# MaTouch_ESP32-S3_7_5_Eink_AI_Mic_Array_V.net
KiCad netlist of a schematic drawn in EAGLE
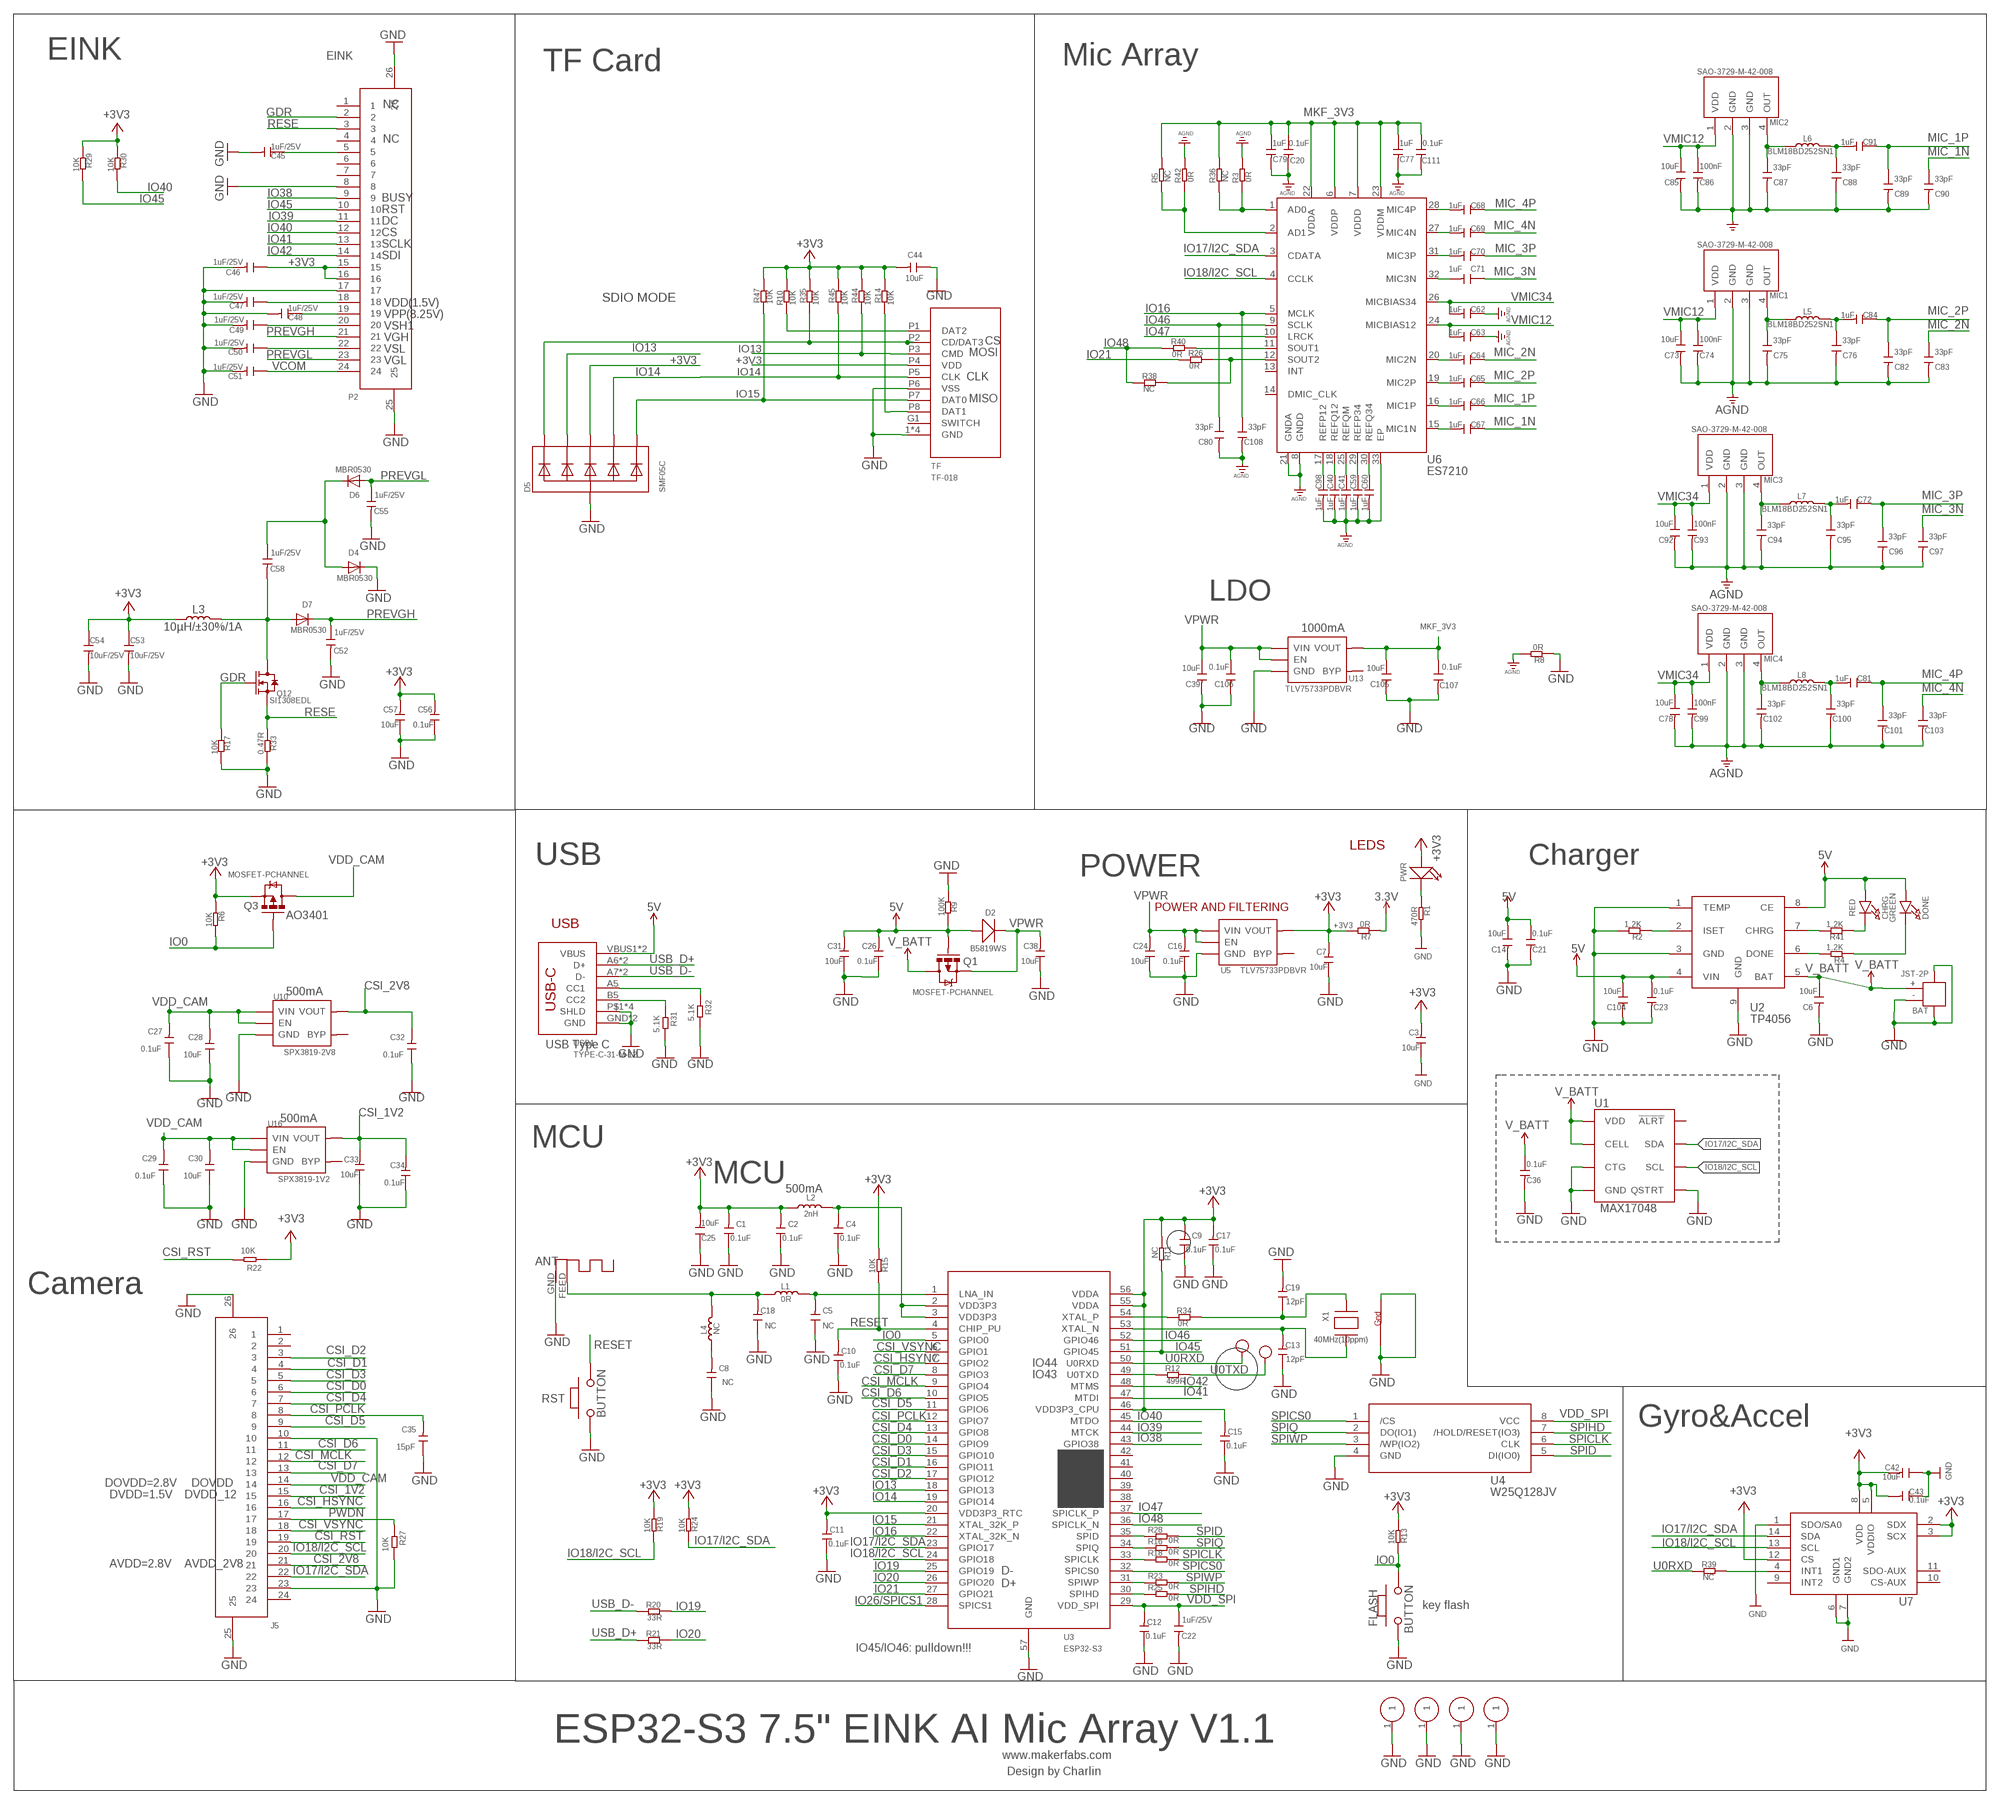
[diagram p0: schematic, sheet 1]

(export (version "E")
  (design (tool "Eeschema 10.0.6"))
  (components
    (comp (ref "ANT1")
      (value "ANTENNA")
      (footprint "eagle-import:RN-ANT")
      (libsource (lib "eagle-import") (part "ANTENNA"))
    )
    (comp (ref "BAT")
      (value "JST-2P")
      (footprint "eagle-import:HW2-SMD-2.0-90D")
      (libsource (lib "eagle-import") (part "JST-2P-SMD'2.0'"))
    )
    (comp (ref "C1")
      (value "0.1uF")
      (footprint "eagle-import:DISCRETE_C0402")
      (libsource (lib "eagle-import") (part "DISCRETE_C-0402"))
    )
    (comp (ref "C2")
      (value "0.1uF")
      (footprint "eagle-import:DISCRETE_C0402")
      (libsource (lib "eagle-import") (part "DISCRETE_C-0402"))
    )
    (comp (ref "C3")
      (value "10uF")
      (footprint "eagle-import:DISCRETE_C0402")
      (libsource (lib "eagle-import") (part "DISCRETE_C-0402"))
    )
    (comp (ref "C4")
      (value "0.1uF")
      (footprint "eagle-import:DISCRETE_C0402")
      (libsource (lib "eagle-import") (part "DISCRETE_C-0402"))
    )
    (comp (ref "C5")
      (value "NC")
      (footprint "eagle-import:DISCRETE_C0402")
      (libsource (lib "eagle-import") (part "DISCRETE_C-0402"))
    )
    (comp (ref "C6")
      (value "10uF")
      (footprint "eagle-import:DISCRETE_C0402")
      (libsource (lib "eagle-import") (part "DISCRETE_C-0402"))
    )
    (comp (ref "C7")
      (value "10uF")
      (footprint "eagle-import:DISCRETE_C0402")
      (libsource (lib "eagle-import") (part "DISCRETE_C-0402"))
    )
    (comp (ref "C8")
      (value "NC")
      (footprint "eagle-import:DISCRETE_C0402")
      (libsource (lib "eagle-import") (part "DISCRETE_C-0402"))
    )
    (comp (ref "C9")
      (value "0.1uF")
      (footprint "eagle-import:DISCRETE_C0402")
      (libsource (lib "eagle-import") (part "DISCRETE_C-0402"))
    )
    (comp (ref "C10")
      (value "0.1uF")
      (footprint "eagle-import:DISCRETE_C0402")
      (libsource (lib "eagle-import") (part "DISCRETE_C-0402"))
    )
    (comp (ref "C11")
      (value "0.1uF")
      (footprint "eagle-import:DISCRETE_C0402")
      (libsource (lib "eagle-import") (part "DISCRETE_C-0402"))
    )
    (comp (ref "C12")
      (value "0.1uF")
      (footprint "eagle-import:DISCRETE_C0402")
      (libsource (lib "eagle-import") (part "DISCRETE_C-0402"))
    )
    (comp (ref "C13")
      (value "12pF")
      (footprint "eagle-import:DISCRETE_C0402")
      (libsource (lib "eagle-import") (part "DISCRETE_C-0402"))
    )
    (comp (ref "C14")
      (value "10uF")
      (footprint "eagle-import:DISCRETE_C0402")
      (libsource (lib "eagle-import") (part "DISCRETE_C-0402"))
    )
    (comp (ref "C15")
      (value "0.1uF")
      (footprint "eagle-import:DISCRETE_C0402")
      (libsource (lib "eagle-import") (part "DISCRETE_C-0402"))
    )
    (comp (ref "C16")
      (value "0.1uF")
      (footprint "eagle-import:DISCRETE_C0402")
      (libsource (lib "eagle-import") (part "DISCRETE_C-0402"))
    )
    (comp (ref "C17")
      (value "0.1uF")
      (footprint "eagle-import:DISCRETE_C0402")
      (libsource (lib "eagle-import") (part "DISCRETE_C-0402"))
    )
    (comp (ref "C18")
      (value "NC")
      (footprint "eagle-import:DISCRETE_C0402")
      (libsource (lib "eagle-import") (part "DISCRETE_C-0402"))
    )
    (comp (ref "C19")
      (value "12pF")
      (footprint "eagle-import:DISCRETE_C0402")
      (libsource (lib "eagle-import") (part "DISCRETE_C-0402"))
    )
    (comp (ref "C20")
      (value "0.1uF")
      (footprint "eagle-import:DISCRETE_C0402")
      (libsource (lib "eagle-import") (part "DISCRETE_C-0402"))
    )
    (comp (ref "C21")
      (value "0.1uF")
      (footprint "eagle-import:DISCRETE_C0402")
      (libsource (lib "eagle-import") (part "DISCRETE_C-0402"))
    )
    (comp (ref "C22")
      (value "1uF/25V")
      (footprint "eagle-import:DISCRETE_C0402")
      (libsource (lib "eagle-import") (part "DISCRETE_C-0402"))
    )
    (comp (ref "C23")
      (value "0.1uF")
      (footprint "eagle-import:DISCRETE_C0402")
      (libsource (lib "eagle-import") (part "DISCRETE_C-0402"))
    )
    (comp (ref "C24")
      (value "10uF")
      (footprint "eagle-import:DISCRETE_C0402")
      (libsource (lib "eagle-import") (part "DISCRETE_C-0402"))
    )
    (comp (ref "C25")
      (value "10uF")
      (footprint "eagle-import:DISCRETE_C0603")
      (libsource (lib "eagle-import") (part "DISCRETE_C-0603"))
    )
    (comp (ref "C26")
      (value "0.1uF")
      (footprint "eagle-import:DISCRETE_C0402")
      (libsource (lib "eagle-import") (part "DISCRETE_C-0402"))
    )
    (comp (ref "C27")
      (value "0.1uF")
      (footprint "eagle-import:DISCRETE_C0402")
      (libsource (lib "eagle-import") (part "DISCRETE_C-0402"))
    )
    (comp (ref "C28")
      (value "10uF")
      (footprint "eagle-import:DISCRETE_C0402")
      (libsource (lib "eagle-import") (part "DISCRETE_C-0402"))
    )
    (comp (ref "C29")
      (value "0.1uF")
      (footprint "eagle-import:DISCRETE_C0402")
      (libsource (lib "eagle-import") (part "DISCRETE_C-0402"))
    )
    (comp (ref "C30")
      (value "10uF")
      (footprint "eagle-import:DISCRETE_C0402")
      (libsource (lib "eagle-import") (part "DISCRETE_C-0402"))
    )
    (comp (ref "C31")
      (value "10uF")
      (footprint "eagle-import:DISCRETE_C0402")
      (libsource (lib "eagle-import") (part "DISCRETE_C-0402"))
    )
    (comp (ref "C32")
      (value "0.1uF")
      (footprint "eagle-import:DISCRETE_C0402")
      (libsource (lib "eagle-import") (part "DISCRETE_C-0402"))
    )
    (comp (ref "C33")
      (value "10uF")
      (footprint "eagle-import:DISCRETE_C0402")
      (libsource (lib "eagle-import") (part "DISCRETE_C-0402"))
    )
    (comp (ref "C34")
      (value "0.1uF")
      (footprint "eagle-import:DISCRETE_C0402")
      (libsource (lib "eagle-import") (part "DISCRETE_C-0402"))
    )
    (comp (ref "C35")
      (value "15pF")
      (footprint "eagle-import:DISCRETE_C0402")
      (libsource (lib "eagle-import") (part "DISCRETE_C-0402"))
    )
    (comp (ref "C36")
      (value "0.1uF")
      (footprint "eagle-import:DISCRETE_C0402")
      (libsource (lib "eagle-import") (part "DISCRETE_C-0402"))
    )
    (comp (ref "C38")
      (value "10uF")
      (footprint "eagle-import:DISCRETE_C0402")
      (libsource (lib "eagle-import") (part "DISCRETE_C-0402"))
    )
    (comp (ref "C39")
      (value "10uF")
      (footprint "eagle-import:DISCRETE_C0402")
      (libsource (lib "eagle-import") (part "DISCRETE_C-0402"))
    )
    (comp (ref "C40")
      (value "1uF")
      (footprint "eagle-import:DISCRETE_C0402")
      (libsource (lib "eagle-import") (part "DISCRETE_C-0402"))
    )
    (comp (ref "C41")
      (value "1uF")
      (footprint "eagle-import:DISCRETE_C0402")
      (libsource (lib "eagle-import") (part "DISCRETE_C-0402"))
    )
    (comp (ref "C42")
      (value "10uF")
      (footprint "eagle-import:DISCRETE_C0402")
      (libsource (lib "eagle-import") (part "DISCRETE_C-0402"))
    )
    (comp (ref "C43")
      (value "0.1uF")
      (footprint "eagle-import:DISCRETE_C0402")
      (libsource (lib "eagle-import") (part "DISCRETE_C-0402"))
    )
    (comp (ref "C44")
      (value "10uF")
      (footprint "eagle-import:DISCRETE_C0402")
      (libsource (lib "eagle-import") (part "DISCRETE_C-0402"))
    )
    (comp (ref "C45")
      (value "1uF/25V")
      (footprint "eagle-import:DISCRETE_C0402")
      (libsource (lib "eagle-import") (part "DISCRETE_C-0402"))
    )
    (comp (ref "C46")
      (value "1uF/25V")
      (footprint "eagle-import:DISCRETE_C0402")
      (libsource (lib "eagle-import") (part "DISCRETE_C-0402"))
    )
    (comp (ref "C47")
      (value "1uF/25V")
      (footprint "eagle-import:DISCRETE_C0402")
      (libsource (lib "eagle-import") (part "DISCRETE_C-0402"))
    )
    (comp (ref "C48")
      (value "1uF/25V")
      (footprint "eagle-import:DISCRETE_C0402")
      (libsource (lib "eagle-import") (part "DISCRETE_C-0402"))
    )
    (comp (ref "C49")
      (value "1uF/25V")
      (footprint "eagle-import:DISCRETE_C0402")
      (libsource (lib "eagle-import") (part "DISCRETE_C-0402"))
    )
    (comp (ref "C50")
      (value "1uF/25V")
      (footprint "eagle-import:DISCRETE_C0402")
      (libsource (lib "eagle-import") (part "DISCRETE_C-0402"))
    )
    (comp (ref "C51")
      (value "1uF/25V")
      (footprint "eagle-import:DISCRETE_C0402")
      (libsource (lib "eagle-import") (part "DISCRETE_C-0402"))
    )
    (comp (ref "C52")
      (value "1uF/25V")
      (footprint "eagle-import:DISCRETE_C0402")
      (libsource (lib "eagle-import") (part "DISCRETE_C-0402"))
    )
    (comp (ref "C53")
      (value "10uF/25V")
      (footprint "eagle-import:C0603")
      (libsource (lib "eagle-import") (part "C-0603"))
    )
    (comp (ref "C54")
      (value "10uF/25V")
      (footprint "eagle-import:C0603")
      (libsource (lib "eagle-import") (part "C-0603"))
    )
    (comp (ref "C55")
      (value "1uF/25V")
      (footprint "eagle-import:DISCRETE_C0402")
      (libsource (lib "eagle-import") (part "DISCRETE_C-0402"))
    )
    (comp (ref "C56")
      (value "0.1uF")
      (footprint "eagle-import:DISCRETE_C0402")
      (libsource (lib "eagle-import") (part "DISCRETE_C-0402"))
    )
    (comp (ref "C57")
      (value "10uF")
      (footprint "eagle-import:DISCRETE_C0402")
      (libsource (lib "eagle-import") (part "DISCRETE_C-0402"))
    )
    (comp (ref "C58")
      (value "1uF/25V")
      (footprint "eagle-import:DISCRETE_C0402")
      (libsource (lib "eagle-import") (part "DISCRETE_C-0402"))
    )
    (comp (ref "C59")
      (value "1uF")
      (footprint "eagle-import:DISCRETE_C0402")
      (libsource (lib "eagle-import") (part "DISCRETE_C-0402"))
    )
    (comp (ref "C60")
      (value "1uF")
      (footprint "eagle-import:DISCRETE_C0402")
      (libsource (lib "eagle-import") (part "DISCRETE_C-0402"))
    )
    (comp (ref "C62")
      (value "1uF")
      (footprint "eagle-import:DISCRETE_C0402")
      (libsource (lib "eagle-import") (part "DISCRETE_C-0402"))
    )
    (comp (ref "C63")
      (value "1uF")
      (footprint "eagle-import:DISCRETE_C0402")
      (libsource (lib "eagle-import") (part "DISCRETE_C-0402"))
    )
    (comp (ref "C64")
      (value "1uF")
      (footprint "eagle-import:DISCRETE_C0402")
      (libsource (lib "eagle-import") (part "DISCRETE_C-0402"))
    )
    (comp (ref "C65")
      (value "1uF")
      (footprint "eagle-import:DISCRETE_C0402")
      (libsource (lib "eagle-import") (part "DISCRETE_C-0402"))
    )
    (comp (ref "C66")
      (value "1uF")
      (footprint "eagle-import:DISCRETE_C0402")
      (libsource (lib "eagle-import") (part "DISCRETE_C-0402"))
    )
    (comp (ref "C67")
      (value "1uF")
      (footprint "eagle-import:DISCRETE_C0402")
      (libsource (lib "eagle-import") (part "DISCRETE_C-0402"))
    )
    (comp (ref "C68")
      (value "1uF")
      (footprint "eagle-import:DISCRETE_C0402")
      (libsource (lib "eagle-import") (part "DISCRETE_C-0402"))
    )
    (comp (ref "C69")
      (value "1uF")
      (footprint "eagle-import:DISCRETE_C0402")
      (libsource (lib "eagle-import") (part "DISCRETE_C-0402"))
    )
    (comp (ref "C70")
      (value "1uF")
      (footprint "eagle-import:DISCRETE_C0402")
      (libsource (lib "eagle-import") (part "DISCRETE_C-0402"))
    )
    (comp (ref "C71")
      (value "1uF")
      (footprint "eagle-import:DISCRETE_C0402")
      (libsource (lib "eagle-import") (part "DISCRETE_C-0402"))
    )
    (comp (ref "C72")
      (value "1uF")
      (footprint "eagle-import:DISCRETE_C0402")
      (libsource (lib "eagle-import") (part "DISCRETE_C-0402"))
    )
    (comp (ref "C73")
      (value "10uF")
      (footprint "eagle-import:DISCRETE_C0402")
      (libsource (lib "eagle-import") (part "DISCRETE_C-0402"))
    )
    (comp (ref "C74")
      (value "100nF")
      (footprint "eagle-import:DISCRETE_C0402")
      (libsource (lib "eagle-import") (part "DISCRETE_C-0402"))
    )
    (comp (ref "C75")
      (value "33pF")
      (footprint "eagle-import:DISCRETE_C0402")
      (libsource (lib "eagle-import") (part "DISCRETE_C-0402"))
    )
    (comp (ref "C76")
      (value "33pF")
      (footprint "eagle-import:DISCRETE_C0402")
      (libsource (lib "eagle-import") (part "DISCRETE_C-0402"))
    )
    (comp (ref "C77")
      (value "1uF")
      (footprint "eagle-import:DISCRETE_C0402")
      (libsource (lib "eagle-import") (part "DISCRETE_C-0402"))
    )
    (comp (ref "C78")
      (value "10uF")
      (footprint "eagle-import:DISCRETE_C0402")
      (libsource (lib "eagle-import") (part "DISCRETE_C-0402"))
    )
    (comp (ref "C79")
      (value "1uF")
      (footprint "eagle-import:DISCRETE_C0402")
      (libsource (lib "eagle-import") (part "DISCRETE_C-0402"))
    )
    (comp (ref "C80")
      (value "33pF")
      (footprint "eagle-import:DISCRETE_C0402")
      (libsource (lib "eagle-import") (part "DISCRETE_C-0402"))
    )
    (comp (ref "C81")
      (value "1uF")
      (footprint "eagle-import:DISCRETE_C0402")
      (libsource (lib "eagle-import") (part "DISCRETE_C-0402"))
    )
    (comp (ref "C82")
      (value "33pF")
      (footprint "eagle-import:DISCRETE_C0402")
      (libsource (lib "eagle-import") (part "DISCRETE_C-0402"))
    )
    (comp (ref "C83")
      (value "33pF")
      (footprint "eagle-import:DISCRETE_C0402")
      (libsource (lib "eagle-import") (part "DISCRETE_C-0402"))
    )
    (comp (ref "C84")
      (value "1uF")
      (footprint "eagle-import:DISCRETE_C0402")
      (libsource (lib "eagle-import") (part "DISCRETE_C-0402"))
    )
    (comp (ref "C85")
      (value "10uF")
      (footprint "eagle-import:DISCRETE_C0402")
      (libsource (lib "eagle-import") (part "DISCRETE_C-0402"))
    )
    (comp (ref "C86")
      (value "100nF")
      (footprint "eagle-import:DISCRETE_C0402")
      (libsource (lib "eagle-import") (part "DISCRETE_C-0402"))
    )
    (comp (ref "C87")
      (value "33pF")
      (footprint "eagle-import:DISCRETE_C0402")
      (libsource (lib "eagle-import") (part "DISCRETE_C-0402"))
    )
    (comp (ref "C88")
      (value "33pF")
      (footprint "eagle-import:DISCRETE_C0402")
      (libsource (lib "eagle-import") (part "DISCRETE_C-0402"))
    )
    (comp (ref "C89")
      (value "33pF")
      (footprint "eagle-import:DISCRETE_C0402")
      (libsource (lib "eagle-import") (part "DISCRETE_C-0402"))
    )
    (comp (ref "C90")
      (value "33pF")
      (footprint "eagle-import:DISCRETE_C0402")
      (libsource (lib "eagle-import") (part "DISCRETE_C-0402"))
    )
    (comp (ref "C91")
      (value "1uF")
      (footprint "eagle-import:DISCRETE_C0402")
      (libsource (lib "eagle-import") (part "DISCRETE_C-0402"))
    )
    (comp (ref "C92")
      (value "10uF")
      (footprint "eagle-import:DISCRETE_C0402")
      (libsource (lib "eagle-import") (part "DISCRETE_C-0402"))
    )
    (comp (ref "C93")
      (value "100nF")
      (footprint "eagle-import:DISCRETE_C0402")
      (libsource (lib "eagle-import") (part "DISCRETE_C-0402"))
    )
    (comp (ref "C94")
      (value "33pF")
      (footprint "eagle-import:DISCRETE_C0402")
      (libsource (lib "eagle-import") (part "DISCRETE_C-0402"))
    )
    (comp (ref "C95")
      (value "33pF")
      (footprint "eagle-import:DISCRETE_C0402")
      (libsource (lib "eagle-import") (part "DISCRETE_C-0402"))
    )
    (comp (ref "C96")
      (value "33pF")
      (footprint "eagle-import:DISCRETE_C0402")
      (libsource (lib "eagle-import") (part "DISCRETE_C-0402"))
    )
    (comp (ref "C97")
      (value "33pF")
      (footprint "eagle-import:DISCRETE_C0402")
      (libsource (lib "eagle-import") (part "DISCRETE_C-0402"))
    )
    (comp (ref "C98")
      (value "1uF")
      (footprint "eagle-import:DISCRETE_C0402")
      (libsource (lib "eagle-import") (part "DISCRETE_C-0402"))
    )
    (comp (ref "C99")
      (value "100nF")
      (footprint "eagle-import:DISCRETE_C0402")
      (libsource (lib "eagle-import") (part "DISCRETE_C-0402"))
    )
    (comp (ref "C100")
      (value "33pF")
      (footprint "eagle-import:DISCRETE_C0402")
      (libsource (lib "eagle-import") (part "DISCRETE_C-0402"))
    )
    (comp (ref "C101")
      (value "33pF")
      (footprint "eagle-import:DISCRETE_C0402")
      (libsource (lib "eagle-import") (part "DISCRETE_C-0402"))
    )
    (comp (ref "C102")
      (value "33pF")
      (footprint "eagle-import:DISCRETE_C0402")
      (libsource (lib "eagle-import") (part "DISCRETE_C-0402"))
    )
    (comp (ref "C103")
      (value "33pF")
      (footprint "eagle-import:DISCRETE_C0402")
      (libsource (lib "eagle-import") (part "DISCRETE_C-0402"))
    )
    (comp (ref "C104")
      (value "10uF")
      (footprint "eagle-import:DISCRETE_C0402")
      (libsource (lib "eagle-import") (part "DISCRETE_C-0402"))
    )
    (comp (ref "C105")
      (value "10uF")
      (footprint "eagle-import:DISCRETE_C0402")
      (libsource (lib "eagle-import") (part "DISCRETE_C-0402"))
    )
    (comp (ref "C106")
      (value "0.1uF")
      (footprint "eagle-import:DISCRETE_C0402")
      (libsource (lib "eagle-import") (part "DISCRETE_C-0402"))
    )
    (comp (ref "C107")
      (value "0.1uF")
      (footprint "eagle-import:DISCRETE_C0402")
      (libsource (lib "eagle-import") (part "DISCRETE_C-0402"))
    )
    (comp (ref "C108")
      (value "33pF")
      (footprint "eagle-import:DISCRETE_C0402")
      (libsource (lib "eagle-import") (part "DISCRETE_C-0402"))
    )
    (comp (ref "C111")
      (value "0.1uF")
      (footprint "eagle-import:DISCRETE_C0402")
      (libsource (lib "eagle-import") (part "DISCRETE_C-0402"))
    )
    (comp (ref "CHRG")
      (value "RED")
      (footprint "eagle-import:CHIPLED_0805_NOOUTLINE")
      (libsource (lib "eagle-import") (part "LED0805_NOOUTLINE"))
    )
    (comp (ref "D2")
      (value "B5819WS")
      (footprint "eagle-import:SOD323")
      (libsource (lib "eagle-import") (part "D'0805'"))
    )
    (comp (ref "D4")
      (value "MBR0530")
      (footprint "eagle-import:SOD-323F")
      (libsource (lib "eagle-import") (part "DIODESOD-323F"))
    )
    (comp (ref "D5")
      (value "SMF05C")
      (footprint "eagle-import:SOT363")
      (libsource (lib "eagle-import") (part "TVSARRAY_5LANE"))
    )
    (comp (ref "D6")
      (value "MBR0530")
      (footprint "eagle-import:SOD-323F")
      (libsource (lib "eagle-import") (part "DIODESOD-323F"))
    )
    (comp (ref "D7")
      (value "MBR0530")
      (footprint "eagle-import:SOD-323F")
      (libsource (lib "eagle-import") (part "DIODESOD-323F"))
    )
    (comp (ref "DONE")
      (value "GREEN")
      (footprint "eagle-import:CHIPLED_0805_NOOUTLINE")
      (libsource (lib "eagle-import") (part "LED0805_NOOUTLINE"))
    )
    (comp (ref "FLASH")
      (value "BUTTON")
      (footprint "eagle-import:157SW")
      (libsource (lib "eagle-import") (part "PB157"))
    )
    (comp (ref "J5")
      (value "FPC-24P")
      (footprint "eagle-import:SMD26-50P-1760L450W")
      (libsource (lib "eagle-import") (part "FPC-24P"))
    )
    (comp (ref "L1")
      (value "0R")
      (footprint "eagle-import:DISCRETE_L0402")
      (libsource (lib "eagle-import") (part "DISCRETE_L0402"))
    )
    (comp (ref "L2")
      (value "2nH")
      (footprint "eagle-import:DISCRETE_L0603")
      (libsource (lib "eagle-import") (part "DISCRETE_L0603"))
    )
    (comp (ref "L3")
      (value "10µH/±30%/1A")
      (footprint "eagle-import:CR54")
      (fields (field (name "PROD_ID") "NDUC-10789"))
      (libsource (lib "eagle-import") (part "INDUCTOR-CR54-47UH"))
    )
    (comp (ref "L4")
      (value "NC")
      (footprint "eagle-import:DISCRETE_L0402")
      (libsource (lib "eagle-import") (part "DISCRETE_L0402"))
    )
    (comp (ref "L5")
      (value "BLM18BD252SN1")
      (footprint "eagle-import:L0603")
      (libsource (lib "eagle-import") (part "INDUCTOR/FERRITE-BEAD'0603'"))
    )
    (comp (ref "L6")
      (value "BLM18BD252SN1")
      (footprint "eagle-import:L0603")
      (libsource (lib "eagle-import") (part "INDUCTOR/FERRITE-BEAD'0603'"))
    )
    (comp (ref "L7")
      (value "BLM18BD252SN1")
      (footprint "eagle-import:L0603")
      (libsource (lib "eagle-import") (part "INDUCTOR/FERRITE-BEAD'0603'"))
    )
    (comp (ref "L8")
      (value "BLM18BD252SN1")
      (footprint "eagle-import:L0603")
      (libsource (lib "eagle-import") (part "INDUCTOR/FERRITE-BEAD'0603'"))
    )
    (comp (ref "MIC1")
      (value "SAO-3729-M-42-008")
      (footprint "eagle-import:MIC4-SMD-3.76X2.95MM")
      (libsource (lib "eagle-import") (part "MIC-MSM421A3729H8-C"))
    )
    (comp (ref "MIC2")
      (value "SAO-3729-M-42-008")
      (footprint "eagle-import:MIC4-SMD-3.76X2.95MM")
      (libsource (lib "eagle-import") (part "MIC-MSM421A3729H8-C"))
    )
    (comp (ref "MIC3")
      (value "SAO-3729-M-42-008")
      (footprint "eagle-import:MIC4-SMD-3.76X2.95MM")
      (libsource (lib "eagle-import") (part "MIC-MSM421A3729H8-C"))
    )
    (comp (ref "MIC4")
      (value "SAO-3729-M-42-008")
      (footprint "eagle-import:MIC4-SMD-3.76X2.95MM")
      (libsource (lib "eagle-import") (part "MIC-MSM421A3729H8-C"))
    )
    (comp (ref "P2")
      (value "FPC-24P")
      (footprint "eagle-import:SMD26-50P-1760L450W")
      (libsource (lib "eagle-import") (part "FPC-24P"))
    )
    (comp (ref "PWR")
      (value "DISCRETE_LED0603")
      (footprint "eagle-import:DISCRETE_LED-0603")
      (libsource (lib "eagle-import") (part "DISCRETE_LED0603"))
    )
    (comp (ref "Q1")
      (value "MOSFET-PCHANNEL")
      (footprint "eagle-import:SOT23-3")
      (libsource (lib "eagle-import") (part "MOSFET-PCHANNEL"))
    )
    (comp (ref "Q3")
      (value "MOSFET-PCHANNEL")
      (footprint "eagle-import:SOT23-3")
      (libsource (lib "eagle-import") (part "MOSFET-PCHANNEL"))
    )
    (comp (ref "Q12")
      (value "SI1308EDL")
      (footprint "eagle-import:SOT23")
      (libsource (lib "eagle-import") (part "MOSFET-N'SOT23'"))
    )
    (comp (ref "R1")
      (value "470R")
      (footprint "eagle-import:DISCRETE_R0402")
      (libsource (lib "eagle-import") (part "DISCRETE_R-0402"))
    )
    (comp (ref "R2")
      (value "1.2K")
      (footprint "eagle-import:DISCRETE_R0402")
      (libsource (lib "eagle-import") (part "DISCRETE_R-0402"))
    )
    (comp (ref "R3")
      (value "0R")
      (footprint "eagle-import:DISCRETE_R0402")
      (libsource (lib "eagle-import") (part "DISCRETE_R-0402"))
    )
    (comp (ref "R4")
      (value "1.2K")
      (footprint "eagle-import:DISCRETE_R0402")
      (libsource (lib "eagle-import") (part "DISCRETE_R-0402"))
    )
    (comp (ref "R5")
      (value "NC")
      (footprint "eagle-import:DISCRETE_R0402")
      (libsource (lib "eagle-import") (part "DISCRETE_R-0402"))
    )
    (comp (ref "R6")
      (value "10K")
      (footprint "eagle-import:DISCRETE_R0402")
      (libsource (lib "eagle-import") (part "DISCRETE_R-0402"))
    )
    (comp (ref "R7")
      (value "0R")
      (footprint "eagle-import:DISCRETE_R0402")
      (libsource (lib "eagle-import") (part "DISCRETE_R-0402"))
    )
    (comp (ref "R8")
      (value "0R")
      (footprint "eagle-import:DISCRETE_R0402")
      (libsource (lib "eagle-import") (part "DISCRETE_R-0402"))
    )
    (comp (ref "R9")
      (value "100K")
      (footprint "eagle-import:DISCRETE_R0402")
      (libsource (lib "eagle-import") (part "DISCRETE_R-0402"))
    )
    (comp (ref "R10")
      (value "10K")
      (footprint "eagle-import:DISCRETE_R0402")
      (libsource (lib "eagle-import") (part "DISCRETE_R-0402"))
    )
    (comp (ref "R11")
      (value "NC")
      (footprint "eagle-import:DISCRETE_R0402")
      (libsource (lib "eagle-import") (part "DISCRETE_R-0402"))
    )
    (comp (ref "R12")
      (value "499R")
      (footprint "eagle-import:DISCRETE_R0402")
      (libsource (lib "eagle-import") (part "DISCRETE_R-0402"))
    )
    (comp (ref "R13")
      (value "10K")
      (footprint "eagle-import:DISCRETE_R0402")
      (libsource (lib "eagle-import") (part "DISCRETE_R-0402"))
    )
    (comp (ref "R14")
      (value "10K")
      (footprint "eagle-import:DISCRETE_R0402")
      (libsource (lib "eagle-import") (part "DISCRETE_R-0402"))
    )
    (comp (ref "R15")
      (value "10K")
      (footprint "eagle-import:DISCRETE_R0402")
      (libsource (lib "eagle-import") (part "DISCRETE_R-0402"))
    )
    (comp (ref "R16")
      (value "0R")
      (footprint "eagle-import:DISCRETE_R0402")
      (libsource (lib "eagle-import") (part "DISCRETE_R-0402"))
    )
    (comp (ref "R17")
      (value "10K")
      (footprint "eagle-import:DISCRETE_R0402")
      (libsource (lib "eagle-import") (part "DISCRETE_R-0402"))
    )
    (comp (ref "R18")
      (value "0R")
      (footprint "eagle-import:DISCRETE_R0402")
      (libsource (lib "eagle-import") (part "DISCRETE_R-0402"))
    )
    (comp (ref "R19")
      (value "10K")
      (footprint "eagle-import:DISCRETE_R0402")
      (libsource (lib "eagle-import") (part "DISCRETE_R-0402"))
    )
    (comp (ref "R20")
      (value "33R")
      (footprint "eagle-import:DISCRETE_R0402")
      (libsource (lib "eagle-import") (part "DISCRETE_R-0402"))
    )
    (comp (ref "R21")
      (value "33R")
      (footprint "eagle-import:DISCRETE_R0402")
      (libsource (lib "eagle-import") (part "DISCRETE_R-0402"))
    )
    (comp (ref "R22")
      (value "10K")
      (footprint "eagle-import:DISCRETE_R0402")
      (libsource (lib "eagle-import") (part "DISCRETE_R-0402"))
    )
    (comp (ref "R23")
      (value "0R")
      (footprint "eagle-import:DISCRETE_R0402")
      (libsource (lib "eagle-import") (part "DISCRETE_R-0402"))
    )
    (comp (ref "R24")
      (value "10K")
      (footprint "eagle-import:DISCRETE_R0402")
      (libsource (lib "eagle-import") (part "DISCRETE_R-0402"))
    )
    (comp (ref "R25")
      (value "0R")
      (footprint "eagle-import:DISCRETE_R0402")
      (libsource (lib "eagle-import") (part "DISCRETE_R-0402"))
    )
    (comp (ref "R26")
      (value "0R")
      (footprint "eagle-import:DISCRETE_R0402")
      (libsource (lib "eagle-import") (part "DISCRETE_R-0402"))
    )
    (comp (ref "R27")
      (value "10K")
      (footprint "eagle-import:DISCRETE_R0402")
      (libsource (lib "eagle-import") (part "DISCRETE_R-0402"))
    )
    (comp (ref "R28")
      (value "0R")
      (footprint "eagle-import:DISCRETE_R0402")
      (libsource (lib "eagle-import") (part "DISCRETE_R-0402"))
    )
    (comp (ref "R29")
      (value "10K")
      (footprint "eagle-import:DISCRETE_R0402")
      (libsource (lib "eagle-import") (part "DISCRETE_R-0402"))
    )
    (comp (ref "R30")
      (value "10K")
      (footprint "eagle-import:DISCRETE_R0402")
      (libsource (lib "eagle-import") (part "DISCRETE_R-0402"))
    )
    (comp (ref "R31")
      (value "5.1K")
      (footprint "eagle-import:DISCRETE_R0402")
      (libsource (lib "eagle-import") (part "DISCRETE_R-0402"))
    )
    (comp (ref "R32")
      (value "5.1K")
      (footprint "eagle-import:DISCRETE_R0402")
      (libsource (lib "eagle-import") (part "DISCRETE_R-0402"))
    )
    (comp (ref "R33")
      (value "0.47R")
      (footprint "eagle-import:DISCRETE_R0402")
      (libsource (lib "eagle-import") (part "DISCRETE_R-0402"))
    )
    (comp (ref "R34")
      (value "0R")
      (footprint "eagle-import:DISCRETE_R0402")
      (libsource (lib "eagle-import") (part "DISCRETE_R-0402"))
    )
    (comp (ref "R35")
      (value "10K")
      (footprint "eagle-import:DISCRETE_R0402")
      (libsource (lib "eagle-import") (part "DISCRETE_R-0402"))
    )
    (comp (ref "R36")
      (value "NC")
      (footprint "eagle-import:DISCRETE_R0402")
      (libsource (lib "eagle-import") (part "DISCRETE_R-0402"))
    )
    (comp (ref "R38")
      (value "NC")
      (footprint "eagle-import:DISCRETE_R0402")
      (libsource (lib "eagle-import") (part "DISCRETE_R-0402"))
    )
    (comp (ref "R39")
      (value "NC")
      (footprint "eagle-import:DISCRETE_R0402")
      (libsource (lib "eagle-import") (part "DISCRETE_R-0402"))
    )
    (comp (ref "R40")
      (value "0R")
      (footprint "eagle-import:DISCRETE_R0402")
      (libsource (lib "eagle-import") (part "DISCRETE_R-0402"))
    )
    (comp (ref "R41")
      (value "1.2K")
      (footprint "eagle-import:DISCRETE_R0402")
      (libsource (lib "eagle-import") (part "DISCRETE_R-0402"))
    )
    (comp (ref "R42")
      (value "0R")
      (footprint "eagle-import:DISCRETE_R0402")
      (libsource (lib "eagle-import") (part "DISCRETE_R-0402"))
    )
    (comp (ref "R44")
      (value "10K")
      (footprint "eagle-import:DISCRETE_R0402")
      (libsource (lib "eagle-import") (part "DISCRETE_R-0402"))
    )
    (comp (ref "R45")
      (value "10K")
      (footprint "eagle-import:DISCRETE_R0402")
      (libsource (lib "eagle-import") (part "DISCRETE_R-0402"))
    )
    (comp (ref "R47")
      (value "10K")
      (footprint "eagle-import:DISCRETE_R0402")
      (libsource (lib "eagle-import") (part "DISCRETE_R-0402"))
    )
    (comp (ref "RST")
      (value "BUTTON")
      (footprint "eagle-import:157SW")
      (libsource (lib "eagle-import") (part "PB157"))
    )
    (comp (ref "RX")
      (value "TEST-POINT'4545'")
      (footprint "eagle-import:TP-D45MIL")
      (fields (field (name "PARTNO") "DNP") (field (name "PARTNO_1") "DNP"))
      (libsource (lib "eagle-import") (part "TEST-POINT'4545'"))
    )
    (comp (ref "S1")
      (value "ONEPIN01")
      (footprint "eagle-import:ONEPIN01")
      (libsource (lib "eagle-import") (part "ONEPIN01"))
    )
    (comp (ref "S2")
      (value "ONEPIN01")
      (footprint "eagle-import:ONEPIN01")
      (libsource (lib "eagle-import") (part "ONEPIN01"))
    )
    (comp (ref "S3")
      (value "ONEPIN01")
      (footprint "eagle-import:ONEPIN01")
      (libsource (lib "eagle-import") (part "ONEPIN01"))
    )
    (comp (ref "S4")
      (value "ONEPIN01")
      (footprint "eagle-import:ONEPIN01")
      (libsource (lib "eagle-import") (part "ONEPIN01"))
    )
    (comp (ref "TF")
      (value "TF-018")
      (footprint "eagle-import:TF-018")
      (libsource (lib "eagle-import") (part "TF-018"))
    )
    (comp (ref "TX")
      (value "TEST-POINT'4545'")
      (footprint "eagle-import:TP-D45MIL")
      (fields (field (name "PARTNO") "DNP") (field (name "PARTNO_1") "DNP"))
      (libsource (lib "eagle-import") (part "TEST-POINT'4545'"))
    )
    (comp (ref "U1")
      (value "MAX17048")
      (footprint "eagle-import:DFN-8")
      (libsource (lib "eagle-import") (part "MAX17048DFN8"))
    )
    (comp (ref "U2")
      (value "TP4056")
      (footprint "eagle-import:SOP8-1.27P")
      (libsource (lib "eagle-import") (part "TP4056"))
    )
    (comp (ref "U3")
      (value "ESP32-S3")
      (footprint "eagle-import:QFN56-7_7MM")
      (libsource (lib "eagle-import") (part "ESP32-S3"))
    )
    (comp (ref "U4")
      (value "W25Q128JV")
      (footprint "eagle-import:SOIC-8-208MIL")
      (libsource (lib "eagle-import") (part "W25Q128JV"))
    )
    (comp (ref "U5")
      (value "TLV75733PDBVR")
      (footprint "eagle-import:SOT23-5")
      (libsource (lib "eagle-import") (part "SPX3819"))
    )
    (comp (ref "U6")
      (value "ES7210")
      (footprint "eagle-import:QFN33-40P400L400W75H-280X280")
      (libsource (lib "eagle-import") (part "ES7210"))
    )
    (comp (ref "U7")
      (value "QMI8658A")
      (footprint "eagle-import:LGA14-50P-300L250W86H")
      (libsource (lib "eagle-import") (part "QMI8658A"))
    )
    (comp (ref "U10")
      (value "SPX3819-2V8")
      (footprint "eagle-import:SOT23-5")
      (libsource (lib "eagle-import") (part "SPX3819"))
    )
    (comp (ref "U13")
      (value "TLV75733PDBVR")
      (footprint "eagle-import:SOT23-5")
      (libsource (lib "eagle-import") (part "SPX3819"))
    )
    (comp (ref "U16")
      (value "SPX3819-1V2")
      (footprint "eagle-import:SOT23-5")
      (libsource (lib "eagle-import") (part "SPX3819"))
    )
    (comp (ref "USB1")
      (value "TYPE-C-31-M-12")
      (footprint "eagle-import:TYPE-C-31-M-12")
      (libsource (lib "eagle-import") (part "TYPE-C-31-M-12"))
    )
    (comp (ref "X1")
      (value "40MHz(10ppm)")
      (footprint "eagle-import:NX3225")
      (libsource (lib "eagle-import") (part "XTAL-4-3225"))
    )
  )
  (nets
    (net (code "1") (name "+3V3") (class "Default")
      (node (ref "C1") (pin "2") (pinfunction "2_2") (pintype "passive"))
      (node (ref "C11") (pin "2") (pinfunction "2_2") (pintype "passive"))
      (node (ref "C15") (pin "2") (pinfunction "2_2") (pintype "passive"))
      (node (ref "C17") (pin "2") (pinfunction "2_2") (pintype "passive"))
      (node (ref "C2") (pin "2") (pinfunction "2_2") (pintype "passive"))
      (node (ref "C25") (pin "2") (pinfunction "2_2") (pintype "passive"))
      (node (ref "C3") (pin "2") (pinfunction "2_2") (pintype "passive"))
      (node (ref "C42") (pin "2") (pinfunction "2_2") (pintype "passive"))
      (node (ref "C43") (pin "2") (pinfunction "2_2") (pintype "passive"))
      (node (ref "C44") (pin "2") (pinfunction "2_2") (pintype "passive"))
      (node (ref "C46") (pin "1") (pinfunction "1_1") (pintype "passive"))
      (node (ref "C53") (pin "1") (pinfunction "1_1") (pintype "passive"))
      (node (ref "C54") (pin "1") (pinfunction "1_1") (pintype "passive"))
      (node (ref "C56") (pin "2") (pinfunction "2_2") (pintype "passive"))
      (node (ref "C57") (pin "2") (pinfunction "2_2") (pintype "passive"))
      (node (ref "C7") (pin "2") (pinfunction "2_2") (pintype "passive"))
      (node (ref "C9") (pin "2") (pinfunction "2_2") (pintype "passive"))
      (node (ref "D5") (pin "4") (pinfunction "C3_4") (pintype "passive"))
      (node (ref "L2") (pin "1") (pinfunction "1_1") (pintype "passive"))
      (node (ref "L3") (pin "P$1") (pinfunction "1_P$1") (pintype "passive"))
      (node (ref "P2") (pin "15") (pinfunction "15_15") (pintype "bidirectional"))
      (node (ref "P2") (pin "16") (pinfunction "16_16") (pintype "bidirectional"))
      (node (ref "PWR") (pin "+") (pinfunction "+_+") (pintype "passive"))
      (node (ref "Q3") (pin "2") (pinfunction "S_2") (pintype "passive"))
      (node (ref "R10") (pin "2") (pinfunction "2_2") (pintype "passive"))
      (node (ref "R11") (pin "2") (pinfunction "2_2") (pintype "passive"))
      (node (ref "R13") (pin "2") (pinfunction "2_2") (pintype "passive"))
      (node (ref "R14") (pin "2") (pinfunction "2_2") (pintype "passive"))
      (node (ref "R15") (pin "2") (pinfunction "2_2") (pintype "passive"))
      (node (ref "R19") (pin "2") (pinfunction "2_2") (pintype "passive"))
      (node (ref "R22") (pin "1") (pinfunction "1_1") (pintype "passive"))
      (node (ref "R24") (pin "2") (pinfunction "2_2") (pintype "passive"))
      (node (ref "R29") (pin "1") (pinfunction "1_1") (pintype "passive"))
      (node (ref "R30") (pin "1") (pinfunction "1_1") (pintype "passive"))
      (node (ref "R35") (pin "2") (pinfunction "2_2") (pintype "passive"))
      (node (ref "R44") (pin "2") (pinfunction "2_2") (pintype "passive"))
      (node (ref "R45") (pin "2") (pinfunction "2_2") (pintype "passive"))
      (node (ref "R47") (pin "2") (pinfunction "2_2") (pintype "passive"))
      (node (ref "R6") (pin "2") (pinfunction "2_2") (pintype "passive"))
      (node (ref "R7") (pin "1") (pinfunction "1_1") (pintype "passive"))
      (node (ref "TF") (pin "P4") (pinfunction "VDD_P4") (pintype "bidirectional"))
      (node (ref "U3") (pin "20") (pinfunction "VDD3P3_RTC_20") (pintype "bidirectional"))
      (node (ref "U3") (pin "46") (pinfunction "VDD3P3_CPU_46") (pintype "bidirectional"))
      (node (ref "U3") (pin "55") (pinfunction "VDDA_55") (pintype "bidirectional"))
      (node (ref "U3") (pin "56") (pinfunction "VDDA_56") (pintype "bidirectional"))
      (node (ref "U5") (pin "5") (pinfunction "VOUT_5") (pintype "bidirectional"))
      (node (ref "U7") (pin "12") (pinfunction "CS_12") (pintype "bidirectional"))
      (node (ref "U7") (pin "2") (pinfunction "SDX_2") (pintype "bidirectional"))
      (node (ref "U7") (pin "3") (pinfunction "SCX_3") (pintype "bidirectional"))
      (node (ref "U7") (pin "5") (pinfunction "VDDIO_5") (pintype "bidirectional"))
      (node (ref "U7") (pin "8") (pinfunction "VDD_8") (pintype "bidirectional"))
    )
    (net (code "2") (name "/CSI_1V2") (class "Default")
      (node (ref "C33") (pin "2") (pinfunction "2_2") (pintype "passive"))
      (node (ref "C34") (pin "2") (pinfunction "2_2") (pintype "passive"))
      (node (ref "J5") (pin "15") (pinfunction "15_15") (pintype "bidirectional"))
      (node (ref "U16") (pin "5") (pinfunction "VOUT_5") (pintype "bidirectional"))
    )
    (net (code "3") (name "/CSI_2V8") (class "Default")
      (node (ref "C32") (pin "2") (pinfunction "2_2") (pintype "passive"))
      (node (ref "J5") (pin "21") (pinfunction "21_21") (pintype "bidirectional"))
      (node (ref "U10") (pin "5") (pinfunction "VOUT_5") (pintype "bidirectional"))
    )
    (net (code "4") (name "/CSI_D0") (class "Default")
      (node (ref "J5") (pin "6") (pinfunction "6_6") (pintype "bidirectional"))
      (node (ref "U3") (pin "14") (pinfunction "GPIO9_14") (pintype "bidirectional"))
    )
    (net (code "5") (name "/CSI_D1") (class "Default")
      (node (ref "J5") (pin "4") (pinfunction "4_4") (pintype "bidirectional"))
      (node (ref "U3") (pin "16") (pinfunction "GPIO11_16") (pintype "bidirectional"))
    )
    (net (code "6") (name "/CSI_D2") (class "Default")
      (node (ref "J5") (pin "3") (pinfunction "3_3") (pintype "bidirectional"))
      (node (ref "U3") (pin "17") (pinfunction "GPIO12_17") (pintype "bidirectional"))
    )
    (net (code "7") (name "/CSI_D3") (class "Default")
      (node (ref "J5") (pin "5") (pinfunction "5_5") (pintype "bidirectional"))
      (node (ref "U3") (pin "15") (pinfunction "GPIO10_15") (pintype "bidirectional"))
    )
    (net (code "8") (name "/CSI_D4") (class "Default")
      (node (ref "J5") (pin "7") (pinfunction "7_7") (pintype "bidirectional"))
      (node (ref "U3") (pin "13") (pinfunction "GPIO8_13") (pintype "bidirectional"))
    )
    (net (code "9") (name "/CSI_D5") (class "Default")
      (node (ref "J5") (pin "9") (pinfunction "9_9") (pintype "bidirectional"))
      (node (ref "U3") (pin "11") (pinfunction "GPIO6_11") (pintype "bidirectional"))
    )
    (net (code "10") (name "/CSI_D6") (class "Default")
      (node (ref "J5") (pin "11") (pinfunction "11_11") (pintype "bidirectional"))
      (node (ref "U3") (pin "10") (pinfunction "GPIO5_10") (pintype "bidirectional"))
    )
    (net (code "11") (name "/CSI_D7") (class "Default")
      (node (ref "J5") (pin "13") (pinfunction "13_13") (pintype "bidirectional"))
      (node (ref "U3") (pin "8") (pinfunction "GPIO3_8") (pintype "bidirectional"))
    )
    (net (code "12") (name "/CSI_HSYNC") (class "Default")
      (node (ref "J5") (pin "16") (pinfunction "16_16") (pintype "bidirectional"))
      (node (ref "U3") (pin "7") (pinfunction "GPIO2_7") (pintype "bidirectional"))
    )
    (net (code "13") (name "/CSI_MCLK") (class "Default")
      (node (ref "J5") (pin "12") (pinfunction "12_12") (pintype "bidirectional"))
      (node (ref "U3") (pin "9") (pinfunction "GPIO4_9") (pintype "bidirectional"))
    )
    (net (code "14") (name "/CSI_PCLK") (class "Default")
      (node (ref "C35") (pin "2") (pinfunction "2_2") (pintype "passive"))
      (node (ref "J5") (pin "8") (pinfunction "8_8") (pintype "bidirectional"))
      (node (ref "U3") (pin "12") (pinfunction "GPIO7_12") (pintype "bidirectional"))
    )
    (net (code "15") (name "/CSI_RST") (class "Default")
      (node (ref "J5") (pin "19") (pinfunction "19_19") (pintype "bidirectional"))
      (node (ref "R22") (pin "2") (pinfunction "2_2") (pintype "passive"))
    )
    (net (code "16") (name "/CSI_VSYNC") (class "Default")
      (node (ref "J5") (pin "18") (pinfunction "18_18") (pintype "bidirectional"))
      (node (ref "U3") (pin "6") (pinfunction "GPIO1_6") (pintype "bidirectional"))
    )
    (net (code "17") (name "/GDR") (class "Default")
      (node (ref "P2") (pin "2") (pinfunction "2_2") (pintype "bidirectional"))
      (node (ref "Q12") (pin "1") (pinfunction "G_1") (pintype "passive"))
      (node (ref "R17") (pin "1") (pinfunction "1_1") (pintype "passive"))
    )
    (net (code "18") (name "/IO0") (class "Default")
      (node (ref "FLASH") (pin "2") (pinfunction "2_2") (pintype "passive"))
      (node (ref "Q3") (pin "1") (pinfunction "G_1") (pintype "passive"))
      (node (ref "R13") (pin "1") (pinfunction "1_1") (pintype "passive"))
      (node (ref "R6") (pin "1") (pinfunction "1_1") (pintype "passive"))
      (node (ref "U3") (pin "5") (pinfunction "GPIO0_5") (pintype "bidirectional"))
    )
    (net (code "19") (name "/IO13") (class "Default")
      (node (ref "D5") (pin "3") (pinfunction "C2_3") (pintype "passive"))
      (node (ref "R44") (pin "1") (pinfunction "1_1") (pintype "passive"))
      (node (ref "TF") (pin "P3") (pinfunction "CMD_P3") (pintype "bidirectional"))
      (node (ref "U3") (pin "18") (pinfunction "GPIO13_18") (pintype "bidirectional"))
    )
    (net (code "20") (name "/IO14") (class "Default")
      (node (ref "D5") (pin "5") (pinfunction "C4_5") (pintype "passive"))
      (node (ref "R45") (pin "1") (pinfunction "1_1") (pintype "passive"))
      (node (ref "TF") (pin "P5") (pinfunction "CLK_P5") (pintype "bidirectional"))
      (node (ref "U3") (pin "19") (pinfunction "GPIO14_19") (pintype "bidirectional"))
    )
    (net (code "21") (name "/IO15") (class "Default")
      (node (ref "D5") (pin "6") (pinfunction "C5_6") (pintype "passive"))
      (node (ref "R47") (pin "1") (pinfunction "1_1") (pintype "passive"))
      (node (ref "TF") (pin "P7") (pinfunction "DAT0_P7") (pintype "bidirectional"))
      (node (ref "U3") (pin "21") (pinfunction "XTAL_32K_P_21") (pintype "bidirectional"))
    )
    (net (code "22") (name "/IO16") (class "Default")
      (node (ref "C108") (pin "1") (pinfunction "1_1") (pintype "passive"))
      (node (ref "U3") (pin "22") (pinfunction "XTAL_32K_N_22") (pintype "bidirectional"))
      (node (ref "U6") (pin "5") (pinfunction "MCLK_5") (pintype "bidirectional"))
    )
    (net (code "23") (name "/IO19") (class "Default")
      (node (ref "R20") (pin "1") (pinfunction "1_1") (pintype "passive"))
      (node (ref "U3") (pin "25") (pinfunction "GPIO19_25") (pintype "bidirectional"))
    )
    (net (code "24") (name "/IO20") (class "Default")
      (node (ref "R21") (pin "1") (pinfunction "1_1") (pintype "passive"))
      (node (ref "U3") (pin "26") (pinfunction "GPIO20_26") (pintype "bidirectional"))
    )
    (net (code "25") (name "/IO21") (class "Default")
      (node (ref "R26") (pin "2") (pinfunction "2_2") (pintype "passive"))
      (node (ref "U3") (pin "27") (pinfunction "GPIO21_27") (pintype "bidirectional"))
    )
    (net (code "26") (name "/IO26{slash}SPICS1") (class "Default")
      (node (ref "U3") (pin "28") (pinfunction "SPICS1_28") (pintype "bidirectional"))
    )
    (net (code "27") (name "/IO38") (class "Default")
      (node (ref "P2") (pin "9") (pinfunction "9_9") (pintype "bidirectional"))
      (node (ref "U3") (pin "43") (pinfunction "GPIO38_43") (pintype "bidirectional"))
    )
    (net (code "28") (name "/IO39") (class "Default")
      (node (ref "P2") (pin "11") (pinfunction "11_11") (pintype "bidirectional"))
      (node (ref "U3") (pin "44") (pinfunction "MTCK_44") (pintype "bidirectional"))
    )
    (net (code "29") (name "/IO40") (class "Default")
      (node (ref "P2") (pin "12") (pinfunction "12_12") (pintype "bidirectional"))
      (node (ref "R30") (pin "2") (pinfunction "2_2") (pintype "passive"))
      (node (ref "U3") (pin "45") (pinfunction "MTDO_45") (pintype "bidirectional"))
    )
    (net (code "30") (name "/IO41") (class "Default")
      (node (ref "P2") (pin "13") (pinfunction "13_13") (pintype "bidirectional"))
      (node (ref "U3") (pin "47") (pinfunction "MTDI_47") (pintype "bidirectional"))
    )
    (net (code "31") (name "/IO42") (class "Default")
      (node (ref "P2") (pin "14") (pinfunction "14_14") (pintype "bidirectional"))
      (node (ref "U3") (pin "48") (pinfunction "MTMS_48") (pintype "bidirectional"))
    )
    (net (code "32") (name "/IO45") (class "Default")
      (node (ref "P2") (pin "10") (pinfunction "10_10") (pintype "bidirectional"))
      (node (ref "R11") (pin "1") (pinfunction "1_1") (pintype "passive"))
      (node (ref "R29") (pin "2") (pinfunction "2_2") (pintype "passive"))
      (node (ref "U3") (pin "51") (pinfunction "GPIO45_51") (pintype "bidirectional"))
    )
    (net (code "33") (name "/IO46") (class "Default")
      (node (ref "C80") (pin "1") (pinfunction "1_1") (pintype "passive"))
      (node (ref "U3") (pin "52") (pinfunction "GPIO46_52") (pintype "bidirectional"))
      (node (ref "U6") (pin "9") (pinfunction "SCLK_9") (pintype "bidirectional"))
    )
    (net (code "34") (name "/IO47") (class "Default")
      (node (ref "U3") (pin "37") (pinfunction "SPICLK_P_37") (pintype "bidirectional"))
      (node (ref "U6") (pin "10") (pinfunction "LRCK_10") (pintype "bidirectional"))
    )
    (net (code "35") (name "/IO48") (class "Default")
      (node (ref "R38") (pin "2") (pinfunction "2_2") (pintype "passive"))
      (node (ref "R40") (pin "2") (pinfunction "2_2") (pintype "passive"))
      (node (ref "U3") (pin "36") (pinfunction "SPICLK_N_36") (pintype "bidirectional"))
    )
    (net (code "36") (name "/MIC_1N") (class "Default")
      (node (ref "C67") (pin "1") (pinfunction "1_1") (pintype "passive"))
      (node (ref "C90") (pin "1") (pinfunction "1_1") (pintype "passive"))
    )
    (net (code "37") (name "/MIC_1P") (class "Default")
      (node (ref "C66") (pin "1") (pinfunction "1_1") (pintype "passive"))
      (node (ref "C89") (pin "1") (pinfunction "1_1") (pintype "passive"))
      (node (ref "C91") (pin "1") (pinfunction "1_1") (pintype "passive"))
    )
    (net (code "38") (name "/MIC_2N") (class "Default")
      (node (ref "C64") (pin "1") (pinfunction "1_1") (pintype "passive"))
      (node (ref "C83") (pin "1") (pinfunction "1_1") (pintype "passive"))
    )
    (net (code "39") (name "/MIC_2P") (class "Default")
      (node (ref "C65") (pin "1") (pinfunction "1_1") (pintype "passive"))
      (node (ref "C82") (pin "1") (pinfunction "1_1") (pintype "passive"))
      (node (ref "C84") (pin "1") (pinfunction "1_1") (pintype "passive"))
    )
    (net (code "40") (name "/MIC_3N") (class "Default")
      (node (ref "C71") (pin "1") (pinfunction "1_1") (pintype "passive"))
      (node (ref "C97") (pin "1") (pinfunction "1_1") (pintype "passive"))
    )
    (net (code "41") (name "/MIC_3P") (class "Default")
      (node (ref "C70") (pin "1") (pinfunction "1_1") (pintype "passive"))
      (node (ref "C72") (pin "1") (pinfunction "1_1") (pintype "passive"))
      (node (ref "C96") (pin "1") (pinfunction "1_1") (pintype "passive"))
    )
    (net (code "42") (name "/MIC_4N") (class "Default")
      (node (ref "C103") (pin "1") (pinfunction "1_1") (pintype "passive"))
      (node (ref "C69") (pin "1") (pinfunction "1_1") (pintype "passive"))
    )
    (net (code "43") (name "/MIC_4P") (class "Default")
      (node (ref "C101") (pin "1") (pinfunction "1_1") (pintype "passive"))
      (node (ref "C68") (pin "1") (pinfunction "1_1") (pintype "passive"))
      (node (ref "C81") (pin "1") (pinfunction "1_1") (pintype "passive"))
    )
    (net (code "44") (name "/MKF_3V3") (class "Default")
      (node (ref "C105") (pin "1") (pinfunction "1_1") (pintype "passive"))
      (node (ref "C107") (pin "1") (pinfunction "1_1") (pintype "passive"))
      (node (ref "C111") (pin "1") (pinfunction "1_1") (pintype "passive"))
      (node (ref "C20") (pin "1") (pinfunction "1_1") (pintype "passive"))
      (node (ref "C77") (pin "1") (pinfunction "1_1") (pintype "passive"))
      (node (ref "C79") (pin "1") (pinfunction "1_1") (pintype "passive"))
      (node (ref "R36") (pin "1") (pinfunction "1_1") (pintype "passive"))
      (node (ref "R5") (pin "1") (pinfunction "1_1") (pintype "passive"))
      (node (ref "U13") (pin "5") (pinfunction "VOUT_5") (pintype "bidirectional"))
      (node (ref "U6") (pin "22") (pinfunction "VDDA_22") (pintype "bidirectional"))
      (node (ref "U6") (pin "23") (pinfunction "VDDM_23") (pintype "bidirectional"))
      (node (ref "U6") (pin "6") (pinfunction "VDDP_6") (pintype "bidirectional"))
      (node (ref "U6") (pin "7") (pinfunction "VDDD_7") (pintype "bidirectional"))
    )
    (net (code "45") (name "/PREVGH") (class "Default")
      (node (ref "C52") (pin "1") (pinfunction "1_1") (pintype "passive"))
      (node (ref "D7") (pin "C") (pinfunction "C_C") (pintype "passive"))
      (node (ref "P2") (pin "21") (pinfunction "21_21") (pintype "bidirectional"))
    )
    (net (code "46") (name "/PREVGL") (class "Default")
      (node (ref "C55") (pin "1") (pinfunction "1_1") (pintype "passive"))
      (node (ref "D6") (pin "A") (pinfunction "A_A") (pintype "passive"))
      (node (ref "P2") (pin "23") (pinfunction "23_23") (pintype "bidirectional"))
    )
    (net (code "47") (name "/PWDN") (class "Default")
      (node (ref "J5") (pin "17") (pinfunction "17_17") (pintype "bidirectional"))
      (node (ref "R27") (pin "1") (pinfunction "1_1") (pintype "passive"))
    )
    (net (code "48") (name "/RESE") (class "Default")
      (node (ref "P2") (pin "3") (pinfunction "3_3") (pintype "bidirectional"))
      (node (ref "Q12") (pin "2") (pinfunction "S_2") (pintype "passive"))
      (node (ref "R33") (pin "1") (pinfunction "1_1") (pintype "passive"))
    )
    (net (code "49") (name "/RESET") (class "Default")
      (node (ref "C10") (pin "2") (pinfunction "2_2") (pintype "passive"))
      (node (ref "R15") (pin "1") (pinfunction "1_1") (pintype "passive"))
      (node (ref "RST") (pin "2") (pinfunction "2_2") (pintype "passive"))
      (node (ref "U3") (pin "4") (pinfunction "CHIP_PU_4") (pintype "bidirectional"))
    )
    (net (code "50") (name "/SPICLK") (class "Default")
      (node (ref "R18") (pin "1") (pinfunction "1_1") (pintype "passive"))
      (node (ref "U4") (pin "6") (pinfunction "CLK_6") (pintype "bidirectional"))
    )
    (net (code "51") (name "/SPICS0") (class "Default")
      (node (ref "U3") (pin "32") (pinfunction "SPICS0_32") (pintype "bidirectional"))
      (node (ref "U4") (pin "1") (pinfunction "/CS_1") (pintype "bidirectional"))
    )
    (net (code "52") (name "/SPID") (class "Default")
      (node (ref "R28") (pin "1") (pinfunction "1_1") (pintype "passive"))
      (node (ref "U4") (pin "5") (pinfunction "DI(IO0)_5") (pintype "bidirectional"))
    )
    (net (code "53") (name "/SPIHD") (class "Default")
      (node (ref "R25") (pin "1") (pinfunction "1_1") (pintype "passive"))
      (node (ref "U4") (pin "7") (pinfunction "/HOLD/RESET(IO3)_7") (pintype "bidirectional"))
    )
    (net (code "54") (name "/SPIQ") (class "Default")
      (node (ref "R16") (pin "1") (pinfunction "1_1") (pintype "passive"))
      (node (ref "U4") (pin "2") (pinfunction "DO(IO1)_2") (pintype "bidirectional"))
    )
    (net (code "55") (name "/SPIWP") (class "Default")
      (node (ref "R23") (pin "1") (pinfunction "1_1") (pintype "passive"))
      (node (ref "U4") (pin "3") (pinfunction "/WP(IO2)_3") (pintype "bidirectional"))
    )
    (net (code "56") (name "/U0RXD") (class "Default")
      (node (ref "R39") (pin "2") (pinfunction "2_2") (pintype "passive"))
      (node (ref "RX") (pin "T") (pinfunction "T_T") (pintype "bidirectional"))
      (node (ref "U3") (pin "50") (pinfunction "U0RXD_50") (pintype "bidirectional"))
    )
    (net (code "57") (name "/U0TXD") (class "Default")
      (node (ref "R12") (pin "1") (pinfunction "1_1") (pintype "passive"))
      (node (ref "TX") (pin "T") (pinfunction "T_T") (pintype "bidirectional"))
    )
    (net (code "58") (name "/USB_D+") (class "Default")
      (node (ref "R21") (pin "2") (pinfunction "2_2") (pintype "passive"))
      (node (ref "USB1") (pin "A6") (pinfunction "D+_A6") (pintype "bidirectional"))
      (node (ref "USB1") (pin "B6") (pinfunction "D+_B6") (pintype "bidirectional"))
    )
    (net (code "59") (name "/USB_D-") (class "Default")
      (node (ref "R20") (pin "2") (pinfunction "2_2") (pintype "passive"))
      (node (ref "USB1") (pin "A7") (pinfunction "D-_A7") (pintype "bidirectional"))
      (node (ref "USB1") (pin "B7") (pinfunction "D-_B7") (pintype "bidirectional"))
    )
    (net (code "60") (name "/VCOM") (class "Default")
      (node (ref "C51") (pin "1") (pinfunction "1_1") (pintype "passive"))
      (node (ref "P2") (pin "24") (pinfunction "24_24") (pintype "bidirectional"))
    )
    (net (code "61") (name "/VDD_CAM") (class "Default")
      (node (ref "C27") (pin "2") (pinfunction "2_2") (pintype "passive"))
      (node (ref "C28") (pin "2") (pinfunction "2_2") (pintype "passive"))
      (node (ref "C29") (pin "2") (pinfunction "2_2") (pintype "passive"))
      (node (ref "C30") (pin "2") (pinfunction "2_2") (pintype "passive"))
      (node (ref "J5") (pin "14") (pinfunction "14_14") (pintype "bidirectional"))
      (node (ref "Q3") (pin "3") (pinfunction "D_3") (pintype "passive"))
      (node (ref "U10") (pin "1") (pinfunction "VIN_1") (pintype "bidirectional"))
      (node (ref "U10") (pin "3") (pinfunction "EN_3") (pintype "bidirectional"))
      (node (ref "U16") (pin "1") (pinfunction "VIN_1") (pintype "bidirectional"))
      (node (ref "U16") (pin "3") (pinfunction "EN_3") (pintype "bidirectional"))
    )
    (net (code "62") (name "/VDD_SPI") (class "Default")
      (node (ref "C12") (pin "2") (pinfunction "2_2") (pintype "passive"))
      (node (ref "C22") (pin "1") (pinfunction "1_1") (pintype "passive"))
      (node (ref "U3") (pin "29") (pinfunction "VDD_SPI_29") (pintype "bidirectional"))
      (node (ref "U4") (pin "8") (pinfunction "VCC_8") (pintype "bidirectional"))
    )
    (net (code "63") (name "/VMIC12") (class "Default")
      (node (ref "C63") (pin "2") (pinfunction "2_2") (pintype "passive"))
      (node (ref "C73") (pin "1") (pinfunction "1_1") (pintype "passive"))
      (node (ref "C74") (pin "1") (pinfunction "1_1") (pintype "passive"))
      (node (ref "C85") (pin "1") (pinfunction "1_1") (pintype "passive"))
      (node (ref "C86") (pin "1") (pinfunction "1_1") (pintype "passive"))
      (node (ref "MIC1") (pin "1") (pinfunction "VDD_1") (pintype "bidirectional"))
      (node (ref "MIC2") (pin "1") (pinfunction "VDD_1") (pintype "bidirectional"))
      (node (ref "U6") (pin "24") (pinfunction "MICBIAS12_24") (pintype "bidirectional"))
    )
    (net (code "64") (name "/VMIC34") (class "Default")
      (node (ref "C62") (pin "2") (pinfunction "2_2") (pintype "passive"))
      (node (ref "C78") (pin "1") (pinfunction "1_1") (pintype "passive"))
      (node (ref "C92") (pin "1") (pinfunction "1_1") (pintype "passive"))
      (node (ref "C93") (pin "1") (pinfunction "1_1") (pintype "passive"))
      (node (ref "C99") (pin "1") (pinfunction "1_1") (pintype "passive"))
      (node (ref "MIC3") (pin "1") (pinfunction "VDD_1") (pintype "bidirectional"))
      (node (ref "MIC4") (pin "1") (pinfunction "VDD_1") (pintype "bidirectional"))
      (node (ref "U6") (pin "26") (pinfunction "MICBIAS34_26") (pintype "bidirectional"))
    )
    (net (code "65") (name "/VPWR") (class "Default")
      (node (ref "C106") (pin "1") (pinfunction "1_1") (pintype "passive"))
      (node (ref "C16") (pin "2") (pinfunction "2_2") (pintype "passive"))
      (node (ref "C24") (pin "2") (pinfunction "2_2") (pintype "passive"))
      (node (ref "C38") (pin "2") (pinfunction "2_2") (pintype "passive"))
      (node (ref "C39") (pin "1") (pinfunction "1_1") (pintype "passive"))
      (node (ref "D2") (pin "-") (pinfunction "-_-") (pintype "passive"))
      (node (ref "Q1") (pin "2") (pinfunction "S_2") (pintype "passive"))
      (node (ref "U13") (pin "1") (pinfunction "VIN_1") (pintype "bidirectional"))
      (node (ref "U13") (pin "3") (pinfunction "EN_3") (pintype "bidirectional"))
      (node (ref "U5") (pin "1") (pinfunction "VIN_1") (pintype "bidirectional"))
      (node (ref "U5") (pin "3") (pinfunction "EN_3") (pintype "bidirectional"))
    )
    (net (code "66") (name "3.3V") (class "Default")
      (node (ref "R7") (pin "2") (pinfunction "2_2") (pintype "passive"))
    )
    (net (code "67") (name "5V") (class "Default")
      (node (ref "C104") (pin "1") (pinfunction "1_1") (pintype "passive"))
      (node (ref "C14") (pin "1") (pinfunction "1_1") (pintype "passive"))
      (node (ref "C21") (pin "1") (pinfunction "1_1") (pintype "passive"))
      (node (ref "C23") (pin "1") (pinfunction "1_1") (pintype "passive"))
      (node (ref "C26") (pin "2") (pinfunction "2_2") (pintype "passive"))
      (node (ref "C31") (pin "2") (pinfunction "2_2") (pintype "passive"))
      (node (ref "CHRG") (pin "A") (pinfunction "A_A") (pintype "passive"))
      (node (ref "D2") (pin "+") (pinfunction "+_+") (pintype "passive"))
      (node (ref "DONE") (pin "A") (pinfunction "A_A") (pintype "passive"))
      (node (ref "Q1") (pin "1") (pinfunction "G_1") (pintype "passive"))
      (node (ref "R9") (pin "2") (pinfunction "2_2") (pintype "passive"))
      (node (ref "U2") (pin "4") (pinfunction "VIN_4") (pintype "bidirectional"))
      (node (ref "U2") (pin "8") (pinfunction "CE_8") (pintype "bidirectional"))
      (node (ref "USB1") (pin "VBUS1") (pinfunction "VBUS_VBUS1") (pintype "bidirectional"))
      (node (ref "USB1") (pin "VBUS2") (pinfunction "VBUS_VBUS2") (pintype "bidirectional"))
    )
    (net (code "68") (name "AGND") (class "Default")
      (node (ref "C100") (pin "2") (pinfunction "2_2") (pintype "passive"))
      (node (ref "C101") (pin "2") (pinfunction "2_2") (pintype "passive"))
      (node (ref "C102") (pin "2") (pinfunction "2_2") (pintype "passive"))
      (node (ref "C103") (pin "2") (pinfunction "2_2") (pintype "passive"))
      (node (ref "C108") (pin "2") (pinfunction "2_2") (pintype "passive"))
      (node (ref "C111") (pin "2") (pinfunction "2_2") (pintype "passive"))
      (node (ref "C20") (pin "2") (pinfunction "2_2") (pintype "passive"))
      (node (ref "C40") (pin "2") (pinfunction "2_2") (pintype "passive"))
      (node (ref "C41") (pin "2") (pinfunction "2_2") (pintype "passive"))
      (node (ref "C59") (pin "2") (pinfunction "2_2") (pintype "passive"))
      (node (ref "C60") (pin "2") (pinfunction "2_2") (pintype "passive"))
      (node (ref "C62") (pin "1") (pinfunction "1_1") (pintype "passive"))
      (node (ref "C63") (pin "1") (pinfunction "1_1") (pintype "passive"))
      (node (ref "C73") (pin "2") (pinfunction "2_2") (pintype "passive"))
      (node (ref "C74") (pin "2") (pinfunction "2_2") (pintype "passive"))
      (node (ref "C75") (pin "2") (pinfunction "2_2") (pintype "passive"))
      (node (ref "C76") (pin "2") (pinfunction "2_2") (pintype "passive"))
      (node (ref "C77") (pin "2") (pinfunction "2_2") (pintype "passive"))
      (node (ref "C78") (pin "2") (pinfunction "2_2") (pintype "passive"))
      (node (ref "C79") (pin "2") (pinfunction "2_2") (pintype "passive"))
      (node (ref "C80") (pin "2") (pinfunction "2_2") (pintype "passive"))
      (node (ref "C82") (pin "2") (pinfunction "2_2") (pintype "passive"))
      (node (ref "C83") (pin "2") (pinfunction "2_2") (pintype "passive"))
      (node (ref "C85") (pin "2") (pinfunction "2_2") (pintype "passive"))
      (node (ref "C86") (pin "2") (pinfunction "2_2") (pintype "passive"))
      (node (ref "C87") (pin "2") (pinfunction "2_2") (pintype "passive"))
      (node (ref "C88") (pin "2") (pinfunction "2_2") (pintype "passive"))
      (node (ref "C89") (pin "2") (pinfunction "2_2") (pintype "passive"))
      (node (ref "C90") (pin "2") (pinfunction "2_2") (pintype "passive"))
      (node (ref "C92") (pin "2") (pinfunction "2_2") (pintype "passive"))
      (node (ref "C93") (pin "2") (pinfunction "2_2") (pintype "passive"))
      (node (ref "C94") (pin "2") (pinfunction "2_2") (pintype "passive"))
      (node (ref "C95") (pin "2") (pinfunction "2_2") (pintype "passive"))
      (node (ref "C96") (pin "2") (pinfunction "2_2") (pintype "passive"))
      (node (ref "C97") (pin "2") (pinfunction "2_2") (pintype "passive"))
      (node (ref "C98") (pin "2") (pinfunction "2_2") (pintype "passive"))
      (node (ref "C99") (pin "2") (pinfunction "2_2") (pintype "passive"))
      (node (ref "MIC1") (pin "2") (pinfunction "GND_2") (pintype "bidirectional"))
      (node (ref "MIC1") (pin "3") (pinfunction "GND_3") (pintype "bidirectional"))
      (node (ref "MIC2") (pin "2") (pinfunction "GND_2") (pintype "bidirectional"))
      (node (ref "MIC2") (pin "3") (pinfunction "GND_3") (pintype "bidirectional"))
      (node (ref "MIC3") (pin "2") (pinfunction "GND_2") (pintype "bidirectional"))
      (node (ref "MIC3") (pin "3") (pinfunction "GND_3") (pintype "bidirectional"))
      (node (ref "MIC4") (pin "2") (pinfunction "GND_2") (pintype "bidirectional"))
      (node (ref "MIC4") (pin "3") (pinfunction "GND_3") (pintype "bidirectional"))
      (node (ref "R3") (pin "1") (pinfunction "1_1") (pintype "passive"))
      (node (ref "R42") (pin "1") (pinfunction "1_1") (pintype "passive"))
      (node (ref "R8") (pin "1") (pinfunction "1_1") (pintype "passive"))
      (node (ref "U6") (pin "21") (pinfunction "GNDA_21") (pintype "bidirectional"))
      (node (ref "U6") (pin "33") (pinfunction "EP_33") (pintype "bidirectional"))
      (node (ref "U6") (pin "8") (pinfunction "GNDD_8") (pintype "bidirectional"))
    )
    (net (code "69") (name "GND") (class "Default")
      (node (ref "ANT1") (pin "GND") (pinfunction "GND_GND") (pintype "passive"))
      (node (ref "BAT") (pin "-") (pinfunction "2_-") (pintype "bidirectional"))
      (node (ref "BAT") (pin "3") (pinfunction "3_3") (pintype "bidirectional"))
      (node (ref "BAT") (pin "4") (pinfunction "4_4") (pintype "bidirectional"))
      (node (ref "C1") (pin "1") (pinfunction "1_1") (pintype "passive"))
      (node (ref "C10") (pin "1") (pinfunction "1_1") (pintype "passive"))
      (node (ref "C104") (pin "2") (pinfunction "2_2") (pintype "passive"))
      (node (ref "C105") (pin "2") (pinfunction "2_2") (pintype "passive"))
      (node (ref "C106") (pin "2") (pinfunction "2_2") (pintype "passive"))
      (node (ref "C107") (pin "2") (pinfunction "2_2") (pintype "passive"))
      (node (ref "C11") (pin "1") (pinfunction "1_1") (pintype "passive"))
      (node (ref "C12") (pin "1") (pinfunction "1_1") (pintype "passive"))
      (node (ref "C13") (pin "1") (pinfunction "1_1") (pintype "passive"))
      (node (ref "C14") (pin "2") (pinfunction "2_2") (pintype "passive"))
      (node (ref "C15") (pin "1") (pinfunction "1_1") (pintype "passive"))
      (node (ref "C16") (pin "1") (pinfunction "1_1") (pintype "passive"))
      (node (ref "C17") (pin "1") (pinfunction "1_1") (pintype "passive"))
      (node (ref "C18") (pin "1") (pinfunction "1_1") (pintype "passive"))
      (node (ref "C19") (pin "2") (pinfunction "2_2") (pintype "passive"))
      (node (ref "C2") (pin "1") (pinfunction "1_1") (pintype "passive"))
      (node (ref "C21") (pin "2") (pinfunction "2_2") (pintype "passive"))
      (node (ref "C22") (pin "2") (pinfunction "2_2") (pintype "passive"))
      (node (ref "C23") (pin "2") (pinfunction "2_2") (pintype "passive"))
      (node (ref "C24") (pin "1") (pinfunction "1_1") (pintype "passive"))
      (node (ref "C25") (pin "1") (pinfunction "1_1") (pintype "passive"))
      (node (ref "C26") (pin "1") (pinfunction "1_1") (pintype "passive"))
      (node (ref "C27") (pin "1") (pinfunction "1_1") (pintype "passive"))
      (node (ref "C28") (pin "1") (pinfunction "1_1") (pintype "passive"))
      (node (ref "C29") (pin "1") (pinfunction "1_1") (pintype "passive"))
      (node (ref "C3") (pin "1") (pinfunction "1_1") (pintype "passive"))
      (node (ref "C30") (pin "1") (pinfunction "1_1") (pintype "passive"))
      (node (ref "C31") (pin "1") (pinfunction "1_1") (pintype "passive"))
      (node (ref "C32") (pin "1") (pinfunction "1_1") (pintype "passive"))
      (node (ref "C33") (pin "1") (pinfunction "1_1") (pintype "passive"))
      (node (ref "C34") (pin "1") (pinfunction "1_1") (pintype "passive"))
      (node (ref "C35") (pin "1") (pinfunction "1_1") (pintype "passive"))
      (node (ref "C36") (pin "2") (pinfunction "2_2") (pintype "passive"))
      (node (ref "C38") (pin "1") (pinfunction "1_1") (pintype "passive"))
      (node (ref "C39") (pin "2") (pinfunction "2_2") (pintype "passive"))
      (node (ref "C4") (pin "1") (pinfunction "1_1") (pintype "passive"))
      (node (ref "C42") (pin "1") (pinfunction "1_1") (pintype "passive"))
      (node (ref "C43") (pin "1") (pinfunction "1_1") (pintype "passive"))
      (node (ref "C44") (pin "1") (pinfunction "1_1") (pintype "passive"))
      (node (ref "C45") (pin "2") (pinfunction "2_2") (pintype "passive"))
      (node (ref "C46") (pin "2") (pinfunction "2_2") (pintype "passive"))
      (node (ref "C47") (pin "2") (pinfunction "2_2") (pintype "passive"))
      (node (ref "C48") (pin "2") (pinfunction "2_2") (pintype "passive"))
      (node (ref "C49") (pin "2") (pinfunction "2_2") (pintype "passive"))
      (node (ref "C5") (pin "1") (pinfunction "1_1") (pintype "passive"))
      (node (ref "C50") (pin "2") (pinfunction "2_2") (pintype "passive"))
      (node (ref "C51") (pin "2") (pinfunction "2_2") (pintype "passive"))
      (node (ref "C52") (pin "2") (pinfunction "2_2") (pintype "passive"))
      (node (ref "C53") (pin "2") (pinfunction "2_2") (pintype "passive"))
      (node (ref "C54") (pin "2") (pinfunction "2_2") (pintype "passive"))
      (node (ref "C55") (pin "2") (pinfunction "2_2") (pintype "passive"))
      (node (ref "C56") (pin "1") (pinfunction "1_1") (pintype "passive"))
      (node (ref "C57") (pin "1") (pinfunction "1_1") (pintype "passive"))
      (node (ref "C6") (pin "2") (pinfunction "2_2") (pintype "passive"))
      (node (ref "C7") (pin "1") (pinfunction "1_1") (pintype "passive"))
      (node (ref "C8") (pin "1") (pinfunction "1_1") (pintype "passive"))
      (node (ref "C9") (pin "1") (pinfunction "1_1") (pintype "passive"))
      (node (ref "D4") (pin "C") (pinfunction "C_C") (pintype "passive"))
      (node (ref "D5") (pin "2") (pinfunction "A_2") (pintype "passive"))
      (node (ref "FLASH") (pin "1") (pinfunction "1_1") (pintype "passive"))
      (node (ref "J5") (pin "10") (pinfunction "10_10") (pintype "bidirectional"))
      (node (ref "J5") (pin "23") (pinfunction "23_23") (pintype "bidirectional"))
      (node (ref "J5") (pin "25") (pinfunction "25_25") (pintype "bidirectional"))
      (node (ref "J5") (pin "26") (pinfunction "26_26") (pintype "bidirectional"))
      (node (ref "P2") (pin "17") (pinfunction "17_17") (pintype "bidirectional"))
      (node (ref "P2") (pin "25") (pinfunction "25_25") (pintype "bidirectional"))
      (node (ref "P2") (pin "26") (pinfunction "26_26") (pintype "bidirectional"))
      (node (ref "P2") (pin "8") (pinfunction "8_8") (pintype "bidirectional"))
      (node (ref "R1") (pin "1") (pinfunction "1_1") (pintype "passive"))
      (node (ref "R17") (pin "2") (pinfunction "2_2") (pintype "passive"))
      (node (ref "R2") (pin "1") (pinfunction "1_1") (pintype "passive"))
      (node (ref "R27") (pin "2") (pinfunction "2_2") (pintype "passive"))
      (node (ref "R31") (pin "2") (pinfunction "2_2") (pintype "passive"))
      (node (ref "R32") (pin "2") (pinfunction "2_2") (pintype "passive"))
      (node (ref "R33") (pin "2") (pinfunction "2_2") (pintype "passive"))
      (node (ref "R8") (pin "2") (pinfunction "2_2") (pintype "passive"))
      (node (ref "R9") (pin "1") (pinfunction "1_1") (pintype "passive"))
      (node (ref "RST") (pin "1") (pinfunction "1_1") (pintype "passive"))
      (node (ref "S1") (pin "1") (pinfunction "1_1") (pintype "bidirectional"))
      (node (ref "S2") (pin "1") (pinfunction "1_1") (pintype "bidirectional"))
      (node (ref "S3") (pin "1") (pinfunction "1_1") (pintype "bidirectional"))
      (node (ref "S4") (pin "1") (pinfunction "1_1") (pintype "bidirectional"))
      (node (ref "TF") (pin "1") (pinfunction "GND_1") (pintype "bidirectional"))
      (node (ref "TF") (pin "2") (pinfunction "GND_2") (pintype "bidirectional"))
      (node (ref "TF") (pin "3") (pinfunction "GND_3") (pintype "bidirectional"))
      (node (ref "TF") (pin "4") (pinfunction "GND_4") (pintype "bidirectional"))
      (node (ref "TF") (pin "P6") (pinfunction "VSS_P6") (pintype "bidirectional"))
      (node (ref "U1") (pin "1") (pinfunction "CTG_1") (pintype "input"))
      (node (ref "U1") (pin "4") (pinfunction "GND_4") (pintype "bidirectional"))
      (node (ref "U1") (pin "6") (pinfunction "QSTRT_6") (pintype "bidirectional"))
      (node (ref "U1") (pin "9") (pinfunction "GND_9") (pintype "bidirectional"))
      (node (ref "U10") (pin "2") (pinfunction "GND_2") (pintype "bidirectional"))
      (node (ref "U13") (pin "2") (pinfunction "GND_2") (pintype "bidirectional"))
      (node (ref "U16") (pin "2") (pinfunction "GND_2") (pintype "bidirectional"))
      (node (ref "U2") (pin "1") (pinfunction "TEMP_1") (pintype "bidirectional"))
      (node (ref "U2") (pin "3") (pinfunction "GND_3") (pintype "bidirectional"))
      (node (ref "U2") (pin "9") (pinfunction "GND_9") (pintype "bidirectional"))
      (node (ref "U3") (pin "57") (pinfunction "GND_57") (pintype "bidirectional"))
      (node (ref "U4") (pin "4") (pinfunction "GND_4") (pintype "bidirectional"))
      (node (ref "U5") (pin "2") (pinfunction "GND_2") (pintype "bidirectional"))
      (node (ref "U7") (pin "1") (pinfunction "SDO/SA0_1") (pintype "bidirectional"))
      (node (ref "U7") (pin "6") (pinfunction "GND1_6") (pintype "bidirectional"))
      (node (ref "U7") (pin "7") (pinfunction "GND2_7") (pintype "bidirectional"))
      (node (ref "USB1") (pin "GND") (pinfunction "GND_GND") (pintype "bidirectional"))
      (node (ref "USB1") (pin "GND2") (pinfunction "GND_GND2") (pintype "bidirectional"))
      (node (ref "USB1") (pin "P$1") (pinfunction "SHLD_P$1") (pintype "bidirectional"))
      (node (ref "USB1") (pin "P$2") (pinfunction "SHLD_P$2") (pintype "bidirectional"))
      (node (ref "USB1") (pin "P$3") (pinfunction "SHLD_P$3") (pintype "bidirectional"))
      (node (ref "USB1") (pin "P$4") (pinfunction "SHLD_P$4") (pintype "bidirectional"))
      (node (ref "X1") (pin "2") (pinfunction "G2_2") (pintype "power_in"))
      (node (ref "X1") (pin "4") (pinfunction "G1_4") (pintype "power_in"))
    )
    (net (code "70") (name "IO17{slash}I2C_SDA") (class "Default")
      (node (ref "J5") (pin "22") (pinfunction "22_22") (pintype "bidirectional"))
      (node (ref "R24") (pin "1") (pinfunction "1_1") (pintype "passive"))
      (node (ref "U1") (pin "8") (pinfunction "SDA_8") (pintype "input"))
      (node (ref "U3") (pin "23") (pinfunction "GPIO17_23") (pintype "bidirectional"))
      (node (ref "U6") (pin "3") (pinfunction "CDATA_3") (pintype "bidirectional"))
      (node (ref "U7") (pin "14") (pinfunction "SDA_14") (pintype "bidirectional"))
    )
    (net (code "71") (name "IO18{slash}I2C_SCL") (class "Default")
      (node (ref "J5") (pin "20") (pinfunction "20_20") (pintype "bidirectional"))
      (node (ref "R19") (pin "1") (pinfunction "1_1") (pintype "passive"))
      (node (ref "U1") (pin "7") (pinfunction "SCL_7") (pintype "output"))
      (node (ref "U3") (pin "24") (pinfunction "GPIO18_24") (pintype "bidirectional"))
      (node (ref "U6") (pin "4") (pinfunction "CCLK_4") (pintype "bidirectional"))
      (node (ref "U7") (pin "13") (pinfunction "SCL_13") (pintype "bidirectional"))
    )
    (net (code "72") (name "Net-(ANT1-PadFEED)") (class "Default")
      (node (ref "ANT1") (pin "FEED") (pinfunction "FEED_FEED") (pintype "passive"))
      (node (ref "C18") (pin "2") (pinfunction "2_2") (pintype "passive"))
      (node (ref "L1") (pin "1") (pinfunction "1_1") (pintype "passive"))
      (node (ref "L4") (pin "2") (pinfunction "2_2") (pintype "passive"))
    )
    (net (code "73") (name "Net-(C4-Pad2)") (class "Default")
      (node (ref "C4") (pin "2") (pinfunction "2_2") (pintype "passive"))
      (node (ref "L2") (pin "2") (pinfunction "2_2") (pintype "passive"))
      (node (ref "U3") (pin "2") (pinfunction "VDD3P3_2") (pintype "bidirectional"))
      (node (ref "U3") (pin "3") (pinfunction "VDD3P3_3") (pintype "bidirectional"))
    )
    (net (code "74") (name "Net-(C8-Pad2)") (class "Default")
      (node (ref "C8") (pin "2") (pinfunction "2_2") (pintype "passive"))
      (node (ref "L4") (pin "1") (pinfunction "1_1") (pintype "passive"))
    )
    (net (code "75") (name "Net-(C45-Pad1)") (class "Default")
      (node (ref "C45") (pin "1") (pinfunction "1_1") (pintype "passive"))
      (node (ref "P2") (pin "5") (pinfunction "5_5") (pintype "bidirectional"))
    )
    (net (code "76") (name "Net-(C47-Pad1)") (class "Default")
      (node (ref "C47") (pin "1") (pinfunction "1_1") (pintype "passive"))
      (node (ref "P2") (pin "18") (pinfunction "18_18") (pintype "bidirectional"))
    )
    (net (code "77") (name "Net-(C48-Pad1)") (class "Default")
      (node (ref "C48") (pin "1") (pinfunction "1_1") (pintype "passive"))
      (node (ref "P2") (pin "19") (pinfunction "19_19") (pintype "bidirectional"))
    )
    (net (code "78") (name "Net-(C49-Pad1)") (class "Default")
      (node (ref "C49") (pin "1") (pinfunction "1_1") (pintype "passive"))
      (node (ref "P2") (pin "20") (pinfunction "20_20") (pintype "bidirectional"))
    )
    (net (code "79") (name "Net-(C50-Pad1)") (class "Default")
      (node (ref "C50") (pin "1") (pinfunction "1_1") (pintype "passive"))
      (node (ref "P2") (pin "22") (pinfunction "22_22") (pintype "bidirectional"))
    )
    (net (code "80") (name "Net-(C58-Pad1)") (class "Default")
      (node (ref "C58") (pin "1") (pinfunction "1_1") (pintype "passive"))
      (node (ref "D4") (pin "A") (pinfunction "A_A") (pintype "passive"))
      (node (ref "D6") (pin "C") (pinfunction "C_C") (pintype "passive"))
    )
    (net (code "81") (name "Net-(C72-Pad2)") (class "Default")
      (node (ref "C72") (pin "2") (pinfunction "2_2") (pintype "passive"))
      (node (ref "C95") (pin "1") (pinfunction "1_1") (pintype "passive"))
      (node (ref "L7") (pin "2") (pinfunction "2_2") (pintype "passive"))
    )
    (net (code "82") (name "Net-(C76-Pad1)") (class "Default")
      (node (ref "C76") (pin "1") (pinfunction "1_1") (pintype "passive"))
      (node (ref "C84") (pin "2") (pinfunction "2_2") (pintype "passive"))
      (node (ref "L5") (pin "2") (pinfunction "2_2") (pintype "passive"))
    )
    (net (code "83") (name "Net-(C88-Pad1)") (class "Default")
      (node (ref "C88") (pin "1") (pinfunction "1_1") (pintype "passive"))
      (node (ref "C91") (pin "2") (pinfunction "2_2") (pintype "passive"))
      (node (ref "L6") (pin "2") (pinfunction "2_2") (pintype "passive"))
    )
    (net (code "84") (name "Net-(C100-Pad1)") (class "Default")
      (node (ref "C100") (pin "1") (pinfunction "1_1") (pintype "passive"))
      (node (ref "C81") (pin "2") (pinfunction "2_2") (pintype "passive"))
      (node (ref "L8") (pin "2") (pinfunction "2_2") (pintype "passive"))
    )
    (net (code "85") (name "Net-(CHRG-PadC)") (class "Default")
      (node (ref "CHRG") (pin "C") (pinfunction "C_C") (pintype "passive"))
      (node (ref "R41") (pin "2") (pinfunction "2_2") (pintype "passive"))
    )
    (net (code "86") (name "Net-(D5-C1)") (class "Default")
      (node (ref "D5") (pin "1") (pinfunction "C1_1") (pintype "passive"))
      (node (ref "R35") (pin "1") (pinfunction "1_1") (pintype "passive"))
      (node (ref "TF") (pin "P2") (pinfunction "CD/DAT3_P2") (pintype "bidirectional"))
    )
    (net (code "87") (name "Net-(DONE-PadC)") (class "Default")
      (node (ref "DONE") (pin "C") (pinfunction "C_C") (pintype "passive"))
      (node (ref "R4") (pin "2") (pinfunction "2_2") (pintype "passive"))
    )
    (net (code "88") (name "Net-(L3-2)") (class "Default")
      (node (ref "C58") (pin "2") (pinfunction "2_2") (pintype "passive"))
      (node (ref "D7") (pin "A") (pinfunction "A_A") (pintype "passive"))
      (node (ref "L3") (pin "P$2") (pinfunction "2_P$2") (pintype "passive"))
      (node (ref "Q12") (pin "3") (pinfunction "D_3") (pintype "passive"))
    )
    (net (code "89") (name "Net-(MIC1-OUT)") (class "Default")
      (node (ref "C75") (pin "1") (pinfunction "1_1") (pintype "passive"))
      (node (ref "L5") (pin "1") (pinfunction "1_1") (pintype "passive"))
      (node (ref "MIC1") (pin "4") (pinfunction "OUT_4") (pintype "bidirectional"))
    )
    (net (code "90") (name "Net-(MIC2-OUT)") (class "Default")
      (node (ref "C87") (pin "1") (pinfunction "1_1") (pintype "passive"))
      (node (ref "L6") (pin "1") (pinfunction "1_1") (pintype "passive"))
      (node (ref "MIC2") (pin "4") (pinfunction "OUT_4") (pintype "bidirectional"))
    )
    (net (code "91") (name "Net-(MIC3-OUT)") (class "Default")
      (node (ref "C94") (pin "1") (pinfunction "1_1") (pintype "passive"))
      (node (ref "L7") (pin "1") (pinfunction "1_1") (pintype "passive"))
      (node (ref "MIC3") (pin "4") (pinfunction "OUT_4") (pintype "bidirectional"))
    )
    (net (code "92") (name "Net-(MIC4-OUT)") (class "Default")
      (node (ref "C102") (pin "1") (pinfunction "1_1") (pintype "passive"))
      (node (ref "L8") (pin "1") (pinfunction "1_1") (pintype "passive"))
      (node (ref "MIC4") (pin "4") (pinfunction "OUT_4") (pintype "bidirectional"))
    )
    (net (code "93") (name "Net-(PWR-Pad-)") (class "Default")
      (node (ref "PWR") (pin "-") (pinfunction "-_-") (pintype "passive"))
      (node (ref "R1") (pin "2") (pinfunction "2_2") (pintype "passive"))
    )
    (net (code "94") (name "Net-(TF-DAT1)") (class "Default")
      (node (ref "R14") (pin "1") (pinfunction "1_1") (pintype "passive"))
      (node (ref "TF") (pin "P8") (pinfunction "DAT1_P8") (pintype "bidirectional"))
    )
    (net (code "95") (name "Net-(TF-DAT2)") (class "Default")
      (node (ref "R10") (pin "1") (pinfunction "1_1") (pintype "passive"))
      (node (ref "TF") (pin "P1") (pinfunction "DAT2_P1") (pintype "bidirectional"))
    )
    (net (code "96") (name "Net-(U2-CHRG)") (class "Default")
      (node (ref "R41") (pin "1") (pinfunction "1_1") (pintype "passive"))
      (node (ref "U2") (pin "7") (pinfunction "CHRG_7") (pintype "bidirectional"))
    )
    (net (code "97") (name "Net-(U2-DONE)") (class "Default")
      (node (ref "R4") (pin "1") (pinfunction "1_1") (pintype "passive"))
      (node (ref "U2") (pin "6") (pinfunction "DONE_6") (pintype "bidirectional"))
    )
    (net (code "98") (name "Net-(U2-ISET)") (class "Default")
      (node (ref "R2") (pin "2") (pinfunction "2_2") (pintype "passive"))
      (node (ref "U2") (pin "2") (pinfunction "ISET_2") (pintype "bidirectional"))
    )
    (net (code "99") (name "Net-(U3-LNA_IN)") (class "Default")
      (node (ref "C5") (pin "2") (pinfunction "2_2") (pintype "passive"))
      (node (ref "L1") (pin "2") (pinfunction "2_2") (pintype "passive"))
      (node (ref "U3") (pin "1") (pinfunction "LNA_IN_1") (pintype "bidirectional"))
    )
    (net (code "100") (name "Net-(U3-SPICLK)") (class "Default")
      (node (ref "R18") (pin "2") (pinfunction "2_2") (pintype "passive"))
      (node (ref "U3") (pin "33") (pinfunction "SPICLK_33") (pintype "bidirectional"))
    )
    (net (code "101") (name "Net-(U3-SPID)") (class "Default")
      (node (ref "R28") (pin "2") (pinfunction "2_2") (pintype "passive"))
      (node (ref "U3") (pin "35") (pinfunction "SPID_35") (pintype "bidirectional"))
    )
    (net (code "102") (name "Net-(U3-SPIHD)") (class "Default")
      (node (ref "R25") (pin "2") (pinfunction "2_2") (pintype "passive"))
      (node (ref "U3") (pin "30") (pinfunction "SPIHD_30") (pintype "bidirectional"))
    )
    (net (code "103") (name "Net-(U3-SPIQ)") (class "Default")
      (node (ref "R16") (pin "2") (pinfunction "2_2") (pintype "passive"))
      (node (ref "U3") (pin "34") (pinfunction "SPIQ_34") (pintype "bidirectional"))
    )
    (net (code "104") (name "Net-(U3-SPIWP)") (class "Default")
      (node (ref "R23") (pin "2") (pinfunction "2_2") (pintype "passive"))
      (node (ref "U3") (pin "31") (pinfunction "SPIWP_31") (pintype "bidirectional"))
    )
    (net (code "105") (name "Net-(U3-U0TXD)") (class "Default")
      (node (ref "R12") (pin "2") (pinfunction "2_2") (pintype "passive"))
      (node (ref "U3") (pin "49") (pinfunction "U0TXD_49") (pintype "bidirectional"))
    )
    (net (code "106") (name "Net-(U3-XTAL_N)") (class "Default")
      (node (ref "C13") (pin "2") (pinfunction "2_2") (pintype "passive"))
      (node (ref "U3") (pin "53") (pinfunction "XTAL_N_53") (pintype "bidirectional"))
      (node (ref "X1") (pin "3") (pinfunction "X2_3") (pintype "bidirectional"))
    )
    (net (code "107") (name "Net-(U3-XTAL_P)") (class "Default")
      (node (ref "R34") (pin "2") (pinfunction "2_2") (pintype "passive"))
      (node (ref "U3") (pin "54") (pinfunction "XTAL_P_54") (pintype "bidirectional"))
    )
    (net (code "108") (name "Net-(U6-AD0)") (class "Default")
      (node (ref "R3") (pin "2") (pinfunction "2_2") (pintype "passive"))
      (node (ref "R36") (pin "2") (pinfunction "2_2") (pintype "passive"))
      (node (ref "U6") (pin "1") (pinfunction "AD0_1") (pintype "bidirectional"))
    )
    (net (code "109") (name "Net-(U6-AD1)") (class "Default")
      (node (ref "R42") (pin "2") (pinfunction "2_2") (pintype "passive"))
      (node (ref "R5") (pin "2") (pinfunction "2_2") (pintype "passive"))
      (node (ref "U6") (pin "2") (pinfunction "AD1_2") (pintype "bidirectional"))
    )
    (net (code "110") (name "Net-(U6-MIC1N)") (class "Default")
      (node (ref "C67") (pin "2") (pinfunction "2_2") (pintype "passive"))
      (node (ref "U6") (pin "15") (pinfunction "MIC1N_15") (pintype "bidirectional"))
    )
    (net (code "111") (name "Net-(U6-MIC1P)") (class "Default")
      (node (ref "C66") (pin "2") (pinfunction "2_2") (pintype "passive"))
      (node (ref "U6") (pin "16") (pinfunction "MIC1P_16") (pintype "bidirectional"))
    )
    (net (code "112") (name "Net-(U6-MIC2N)") (class "Default")
      (node (ref "C64") (pin "2") (pinfunction "2_2") (pintype "passive"))
      (node (ref "U6") (pin "20") (pinfunction "MIC2N_20") (pintype "bidirectional"))
    )
    (net (code "113") (name "Net-(U6-MIC2P)") (class "Default")
      (node (ref "C65") (pin "2") (pinfunction "2_2") (pintype "passive"))
      (node (ref "U6") (pin "19") (pinfunction "MIC2P_19") (pintype "bidirectional"))
    )
    (net (code "114") (name "Net-(U6-MIC3N)") (class "Default")
      (node (ref "C71") (pin "2") (pinfunction "2_2") (pintype "passive"))
      (node (ref "U6") (pin "32") (pinfunction "MIC3N_32") (pintype "bidirectional"))
    )
    (net (code "115") (name "Net-(U6-MIC3P)") (class "Default")
      (node (ref "C70") (pin "2") (pinfunction "2_2") (pintype "passive"))
      (node (ref "U6") (pin "31") (pinfunction "MIC3P_31") (pintype "bidirectional"))
    )
    (net (code "116") (name "Net-(U6-MIC4N)") (class "Default")
      (node (ref "C69") (pin "2") (pinfunction "2_2") (pintype "passive"))
      (node (ref "U6") (pin "27") (pinfunction "MIC4N_27") (pintype "bidirectional"))
    )
    (net (code "117") (name "Net-(U6-MIC4P)") (class "Default")
      (node (ref "C68") (pin "2") (pinfunction "2_2") (pintype "passive"))
      (node (ref "U6") (pin "28") (pinfunction "MIC4P_28") (pintype "bidirectional"))
    )
    (net (code "118") (name "Net-(U6-REFP12)") (class "Default")
      (node (ref "C98") (pin "1") (pinfunction "1_1") (pintype "passive"))
      (node (ref "U6") (pin "17") (pinfunction "REFP12_17") (pintype "bidirectional"))
    )
    (net (code "119") (name "Net-(U6-REFP34)") (class "Default")
      (node (ref "C59") (pin "1") (pinfunction "1_1") (pintype "passive"))
      (node (ref "U6") (pin "29") (pinfunction "REFP34_29") (pintype "bidirectional"))
    )
    (net (code "120") (name "Net-(U6-REFQ12)") (class "Default")
      (node (ref "C40") (pin "1") (pinfunction "1_1") (pintype "passive"))
      (node (ref "U6") (pin "18") (pinfunction "REFQ12_18") (pintype "bidirectional"))
    )
    (net (code "121") (name "Net-(U6-REFQ34)") (class "Default")
      (node (ref "C60") (pin "1") (pinfunction "1_1") (pintype "passive"))
      (node (ref "U6") (pin "30") (pinfunction "REFQ34_30") (pintype "bidirectional"))
    )
    (net (code "122") (name "Net-(U6-REFQM)") (class "Default")
      (node (ref "C41") (pin "1") (pinfunction "1_1") (pintype "passive"))
      (node (ref "U6") (pin "25") (pinfunction "REFQM_25") (pintype "bidirectional"))
    )
    (net (code "123") (name "Net-(U6-SOUT1)") (class "Default")
      (node (ref "R40") (pin "1") (pinfunction "1_1") (pintype "passive"))
      (node (ref "U6") (pin "11") (pinfunction "SOUT1_11") (pintype "bidirectional"))
    )
    (net (code "124") (name "Net-(U6-SOUT2)") (class "Default")
      (node (ref "R26") (pin "1") (pinfunction "1_1") (pintype "passive"))
      (node (ref "R38") (pin "1") (pinfunction "1_1") (pintype "passive"))
      (node (ref "U6") (pin "12") (pinfunction "SOUT2_12") (pintype "bidirectional"))
    )
    (net (code "125") (name "Net-(U7-INT1)") (class "Default")
      (node (ref "R39") (pin "1") (pinfunction "1_1") (pintype "passive"))
      (node (ref "U7") (pin "4") (pinfunction "INT1_4") (pintype "bidirectional"))
    )
    (net (code "126") (name "Net-(USB1-CC1)") (class "Default")
      (node (ref "R32") (pin "1") (pinfunction "1_1") (pintype "passive"))
      (node (ref "USB1") (pin "A5") (pinfunction "CC1_A5") (pintype "bidirectional"))
    )
    (net (code "127") (name "Net-(USB1-CC2)") (class "Default")
      (node (ref "R31") (pin "1") (pinfunction "1_1") (pintype "passive"))
      (node (ref "USB1") (pin "B5") (pinfunction "CC2_B5") (pintype "bidirectional"))
    )
    (net (code "128") (name "Net-(X1-X1)") (class "Default")
      (node (ref "C19") (pin "1") (pinfunction "1_1") (pintype "passive"))
      (node (ref "R34") (pin "1") (pinfunction "1_1") (pintype "passive"))
      (node (ref "X1") (pin "1") (pinfunction "X1_1") (pintype "bidirectional"))
    )
    (net (code "129") (name "V_BATT") (class "Default")
      (node (ref "BAT") (pin "+") (pinfunction "1_+") (pintype "bidirectional"))
      (node (ref "C36") (pin "1") (pinfunction "1_1") (pintype "passive"))
      (node (ref "C6") (pin "1") (pinfunction "1_1") (pintype "passive"))
      (node (ref "Q1") (pin "3") (pinfunction "D_3") (pintype "passive"))
      (node (ref "U1") (pin "2") (pinfunction "CELL_2") (pintype "input"))
      (node (ref "U1") (pin "3") (pinfunction "VDD_3") (pintype "bidirectional"))
      (node (ref "U2") (pin "5") (pinfunction "BAT_5") (pintype "bidirectional"))
    )
    (net (code "130") (name "unconnected-(J5-Pad1)") (class "Default")
      (node (ref "J5") (pin "1") (pinfunction "1_1") (pintype "bidirectional"))
    )
    (net (code "131") (name "unconnected-(J5-Pad2)") (class "Default")
      (node (ref "J5") (pin "2") (pinfunction "2_2") (pintype "bidirectional"))
    )
    (net (code "132") (name "unconnected-(J5-Pad24)") (class "Default")
      (node (ref "J5") (pin "24") (pinfunction "24_24") (pintype "bidirectional"))
    )
    (net (code "133") (name "unconnected-(P2-Pad1)") (class "Default")
      (node (ref "P2") (pin "1") (pinfunction "1_1") (pintype "bidirectional"))
    )
    (net (code "134") (name "unconnected-(P2-Pad4)") (class "Default")
      (node (ref "P2") (pin "4") (pinfunction "4_4") (pintype "bidirectional"))
    )
    (net (code "135") (name "unconnected-(P2-Pad6)") (class "Default")
      (node (ref "P2") (pin "6") (pinfunction "6_6") (pintype "bidirectional"))
    )
    (net (code "136") (name "unconnected-(P2-Pad7)") (class "Default")
      (node (ref "P2") (pin "7") (pinfunction "7_7") (pintype "bidirectional"))
    )
    (net (code "137") (name "unconnected-(TF-SWITCH-PadG1)") (class "Default")
      (node (ref "TF") (pin "G1") (pinfunction "SWITCH_G1") (pintype "bidirectional"))
    )
    (net (code "138") (name "unconnected-(U1-~{ALRT}-Pad5)") (class "Default")
      (node (ref "U1") (pin "5") (pinfunction "~{ALRT}_5") (pintype "bidirectional"))
    )
    (net (code "139") (name "unconnected-(U3-GPIO33-Pad38)") (class "Default")
      (node (ref "U3") (pin "38") (pinfunction "GPIO33_38") (pintype "bidirectional"))
    )
    (net (code "140") (name "unconnected-(U3-GPIO34-Pad39)") (class "Default")
      (node (ref "U3") (pin "39") (pinfunction "GPIO34_39") (pintype "bidirectional"))
    )
    (net (code "141") (name "unconnected-(U3-GPIO35-Pad40)") (class "Default")
      (node (ref "U3") (pin "40") (pinfunction "GPIO35_40") (pintype "bidirectional"))
    )
    (net (code "142") (name "unconnected-(U3-GPIO36-Pad41)") (class "Default")
      (node (ref "U3") (pin "41") (pinfunction "GPIO36_41") (pintype "bidirectional"))
    )
    (net (code "143") (name "unconnected-(U3-GPIO37-Pad42)") (class "Default")
      (node (ref "U3") (pin "42") (pinfunction "GPIO37_42") (pintype "bidirectional"))
    )
    (net (code "144") (name "unconnected-(U5-BYP-Pad4)") (class "Default")
      (node (ref "U5") (pin "4") (pinfunction "BYP_4") (pintype "bidirectional"))
    )
    (net (code "145") (name "unconnected-(U6-DMIC_CLK-Pad14)") (class "Default")
      (node (ref "U6") (pin "14") (pinfunction "DMIC_CLK_14") (pintype "bidirectional"))
    )
    (net (code "146") (name "unconnected-(U6-INT-Pad13)") (class "Default")
      (node (ref "U6") (pin "13") (pinfunction "INT_13") (pintype "bidirectional"))
    )
    (net (code "147") (name "unconnected-(U7-CS-AUX-Pad10)") (class "Default")
      (node (ref "U7") (pin "10") (pinfunction "CS-AUX_10") (pintype "bidirectional"))
    )
    (net (code "148") (name "unconnected-(U7-INT2-Pad9)") (class "Default")
      (node (ref "U7") (pin "9") (pinfunction "INT2_9") (pintype "bidirectional"))
    )
    (net (code "149") (name "unconnected-(U7-SDO-AUX-Pad11)") (class "Default")
      (node (ref "U7") (pin "11") (pinfunction "SDO-AUX_11") (pintype "bidirectional"))
    )
    (net (code "150") (name "unconnected-(U10-BYP-Pad4)") (class "Default")
      (node (ref "U10") (pin "4") (pinfunction "BYP_4") (pintype "bidirectional"))
    )
    (net (code "151") (name "unconnected-(U13-BYP-Pad4)") (class "Default")
      (node (ref "U13") (pin "4") (pinfunction "BYP_4") (pintype "bidirectional"))
    )
    (net (code "152") (name "unconnected-(U16-BYP-Pad4)") (class "Default")
      (node (ref "U16") (pin "4") (pinfunction "BYP_4") (pintype "bidirectional"))
    )
  )
)
